# ACB-Light-R1_0-J05.net
KiCad netlist of a schematic drawn in EAGLE
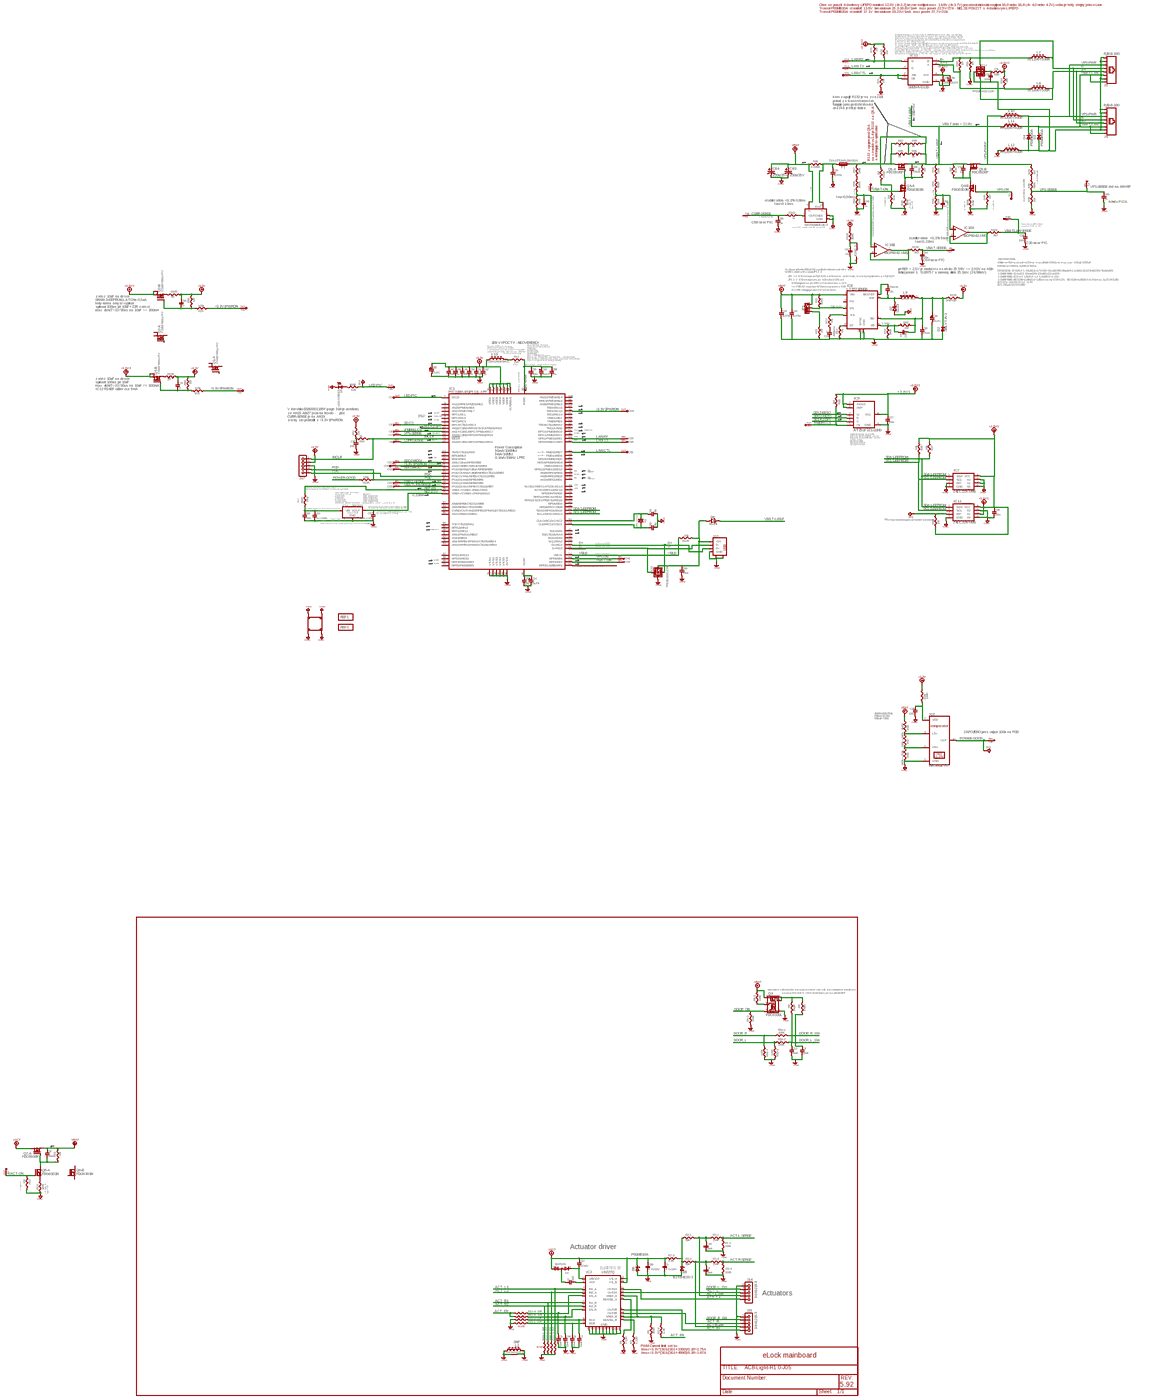
[diagram p0: schematic, sheet 1, overview]
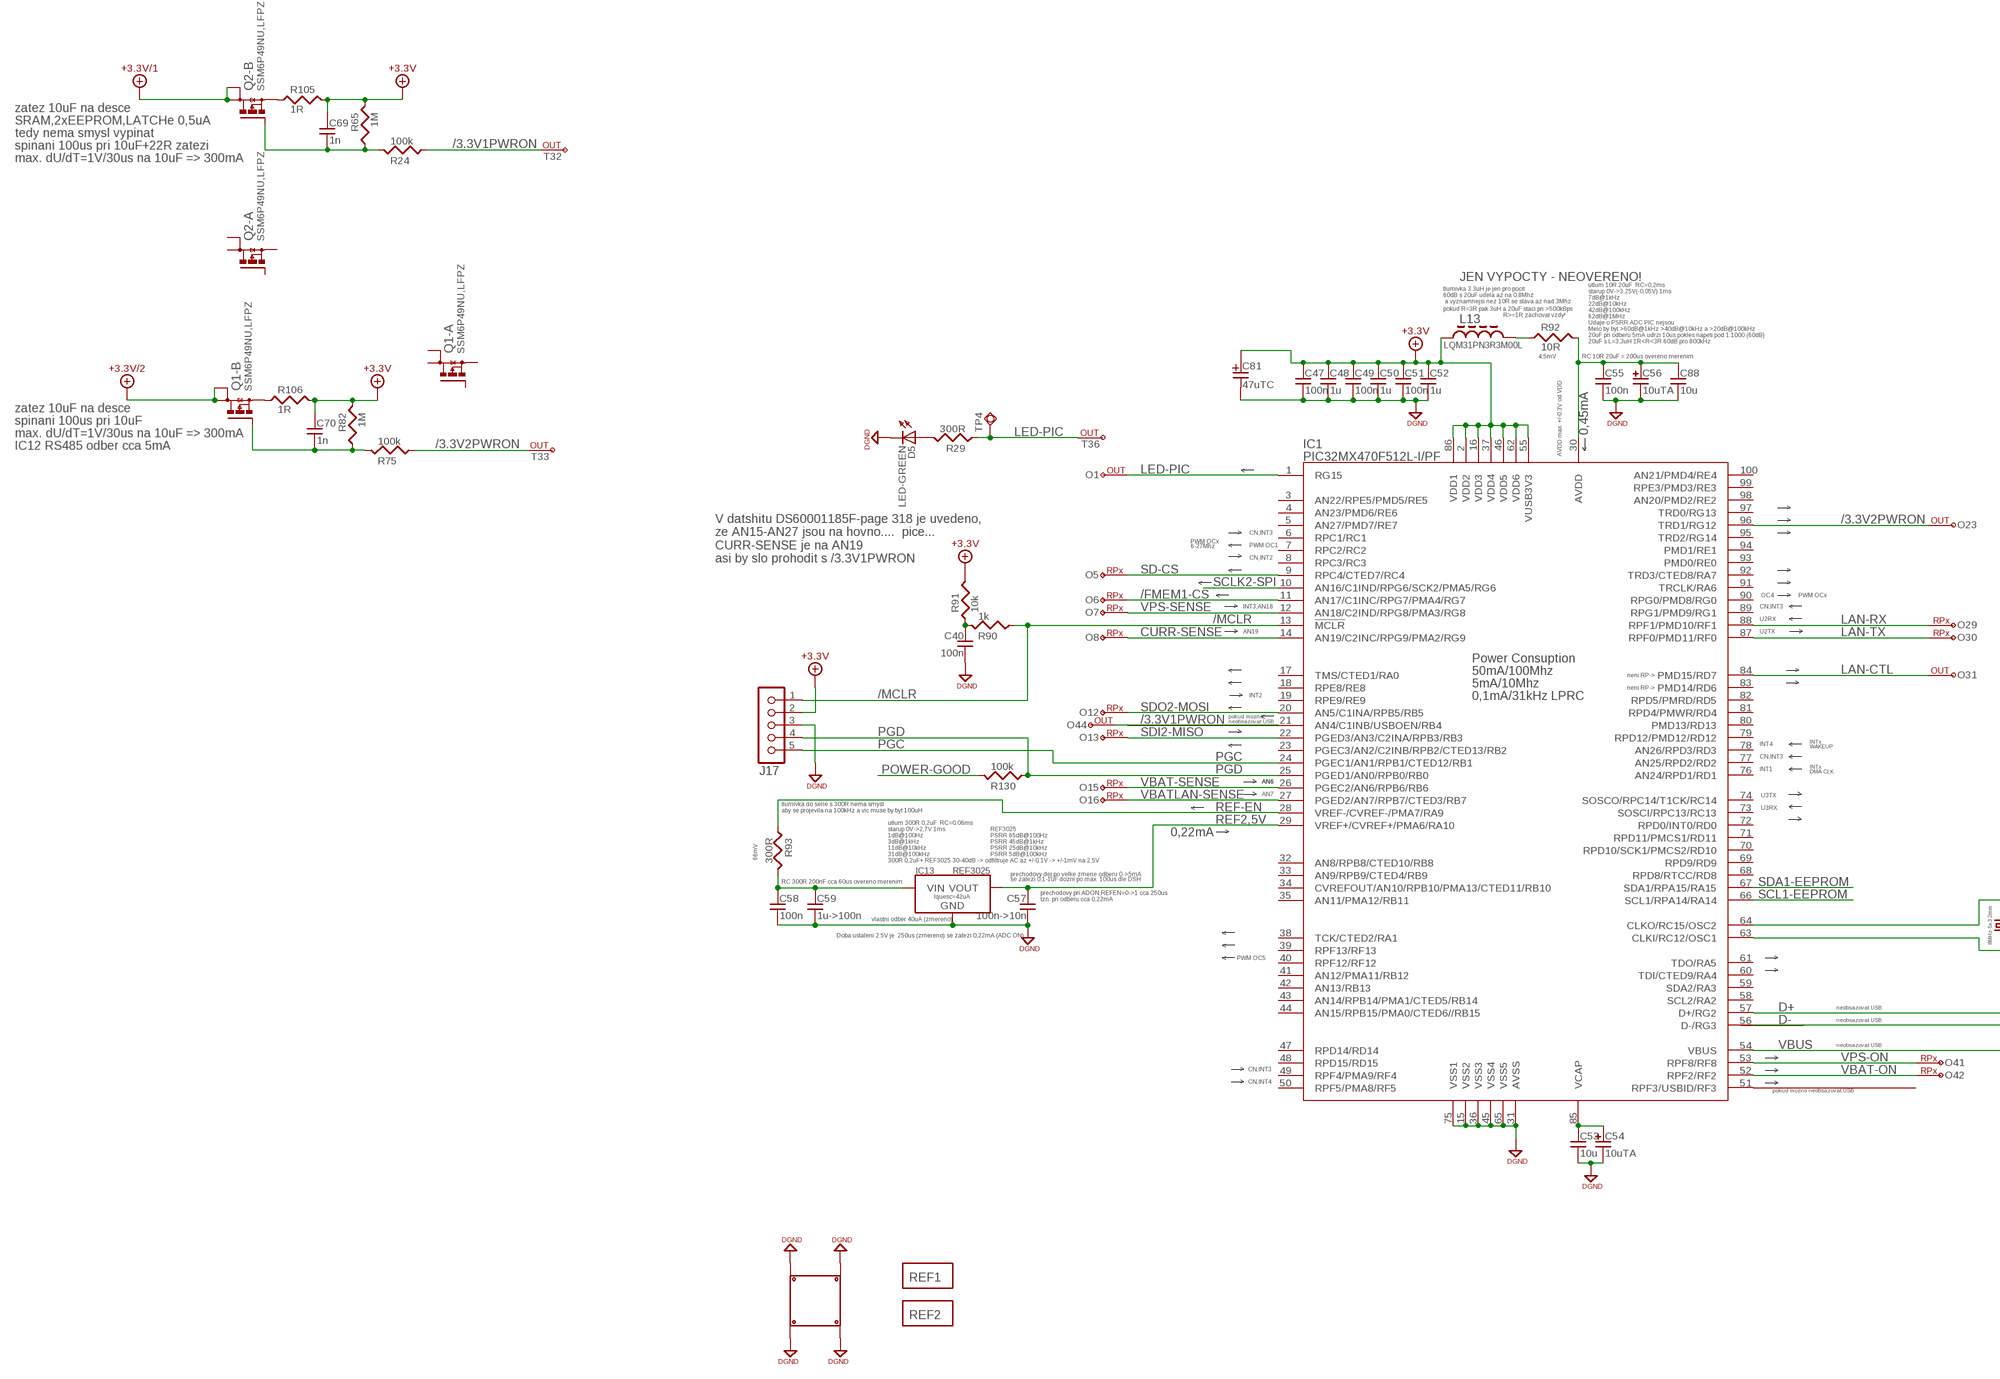
[diagram p1: schematic, sheet 1, part 1 of 5]
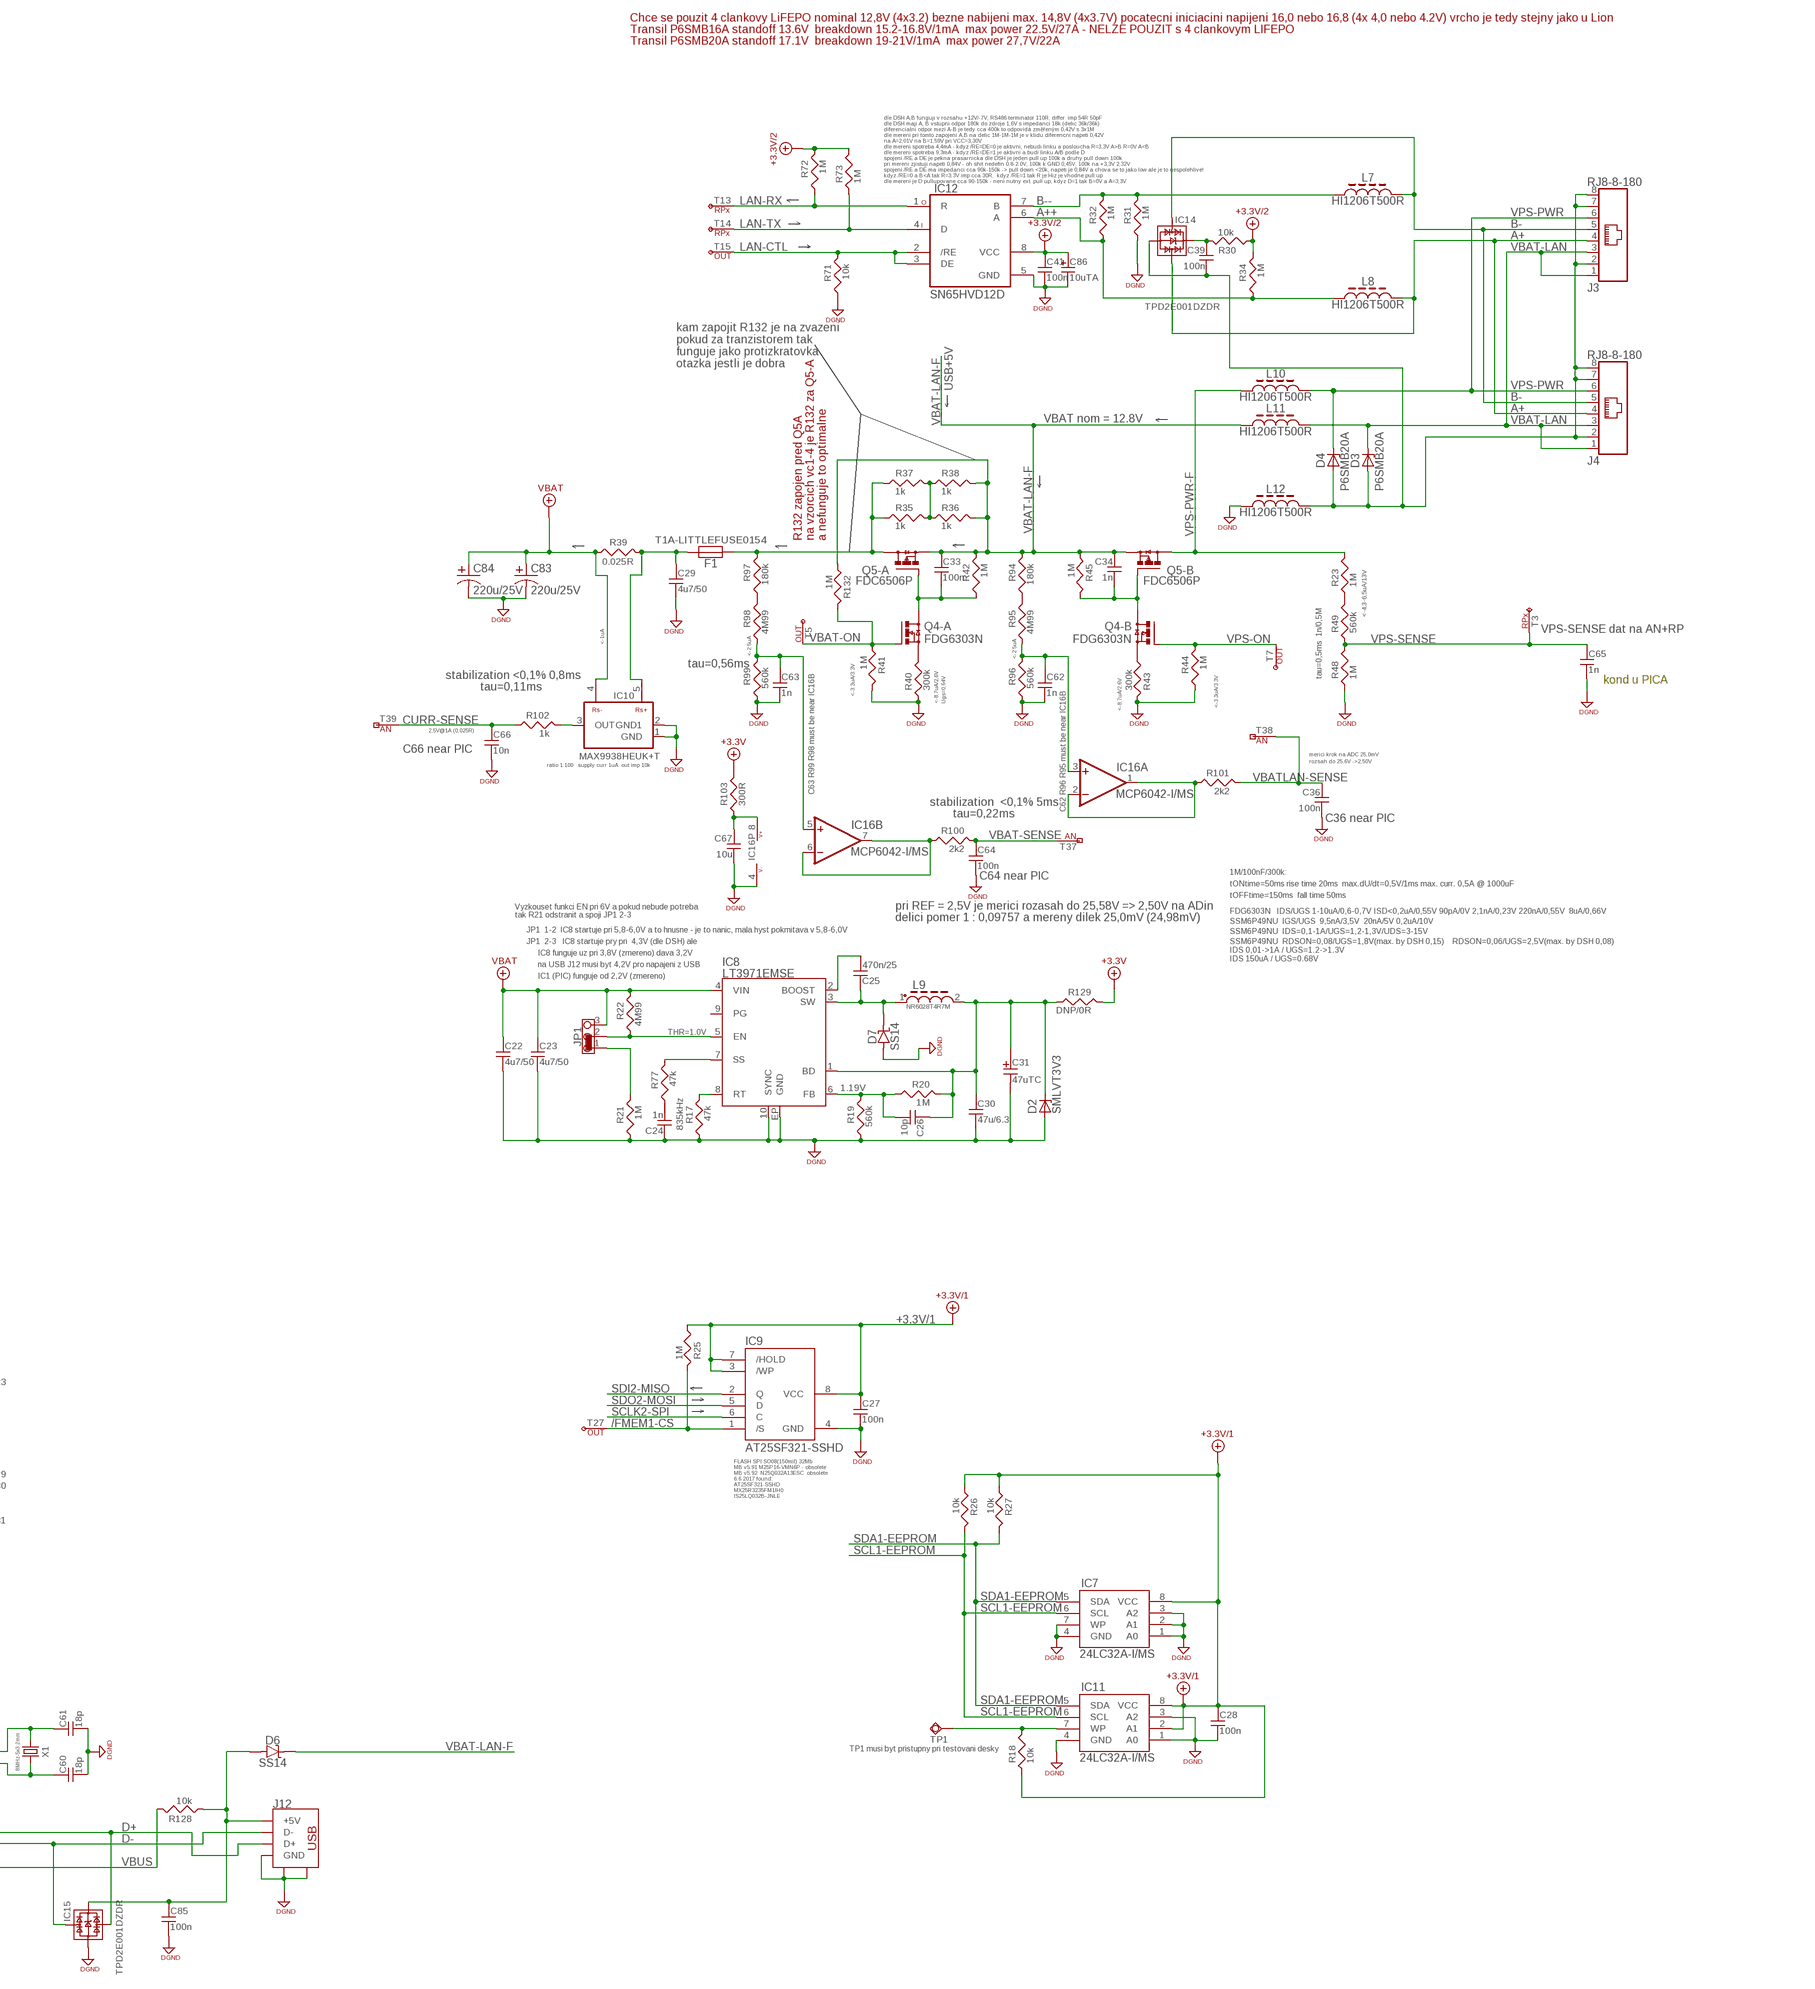
[diagram p2: schematic, sheet 1, part 2 of 5]
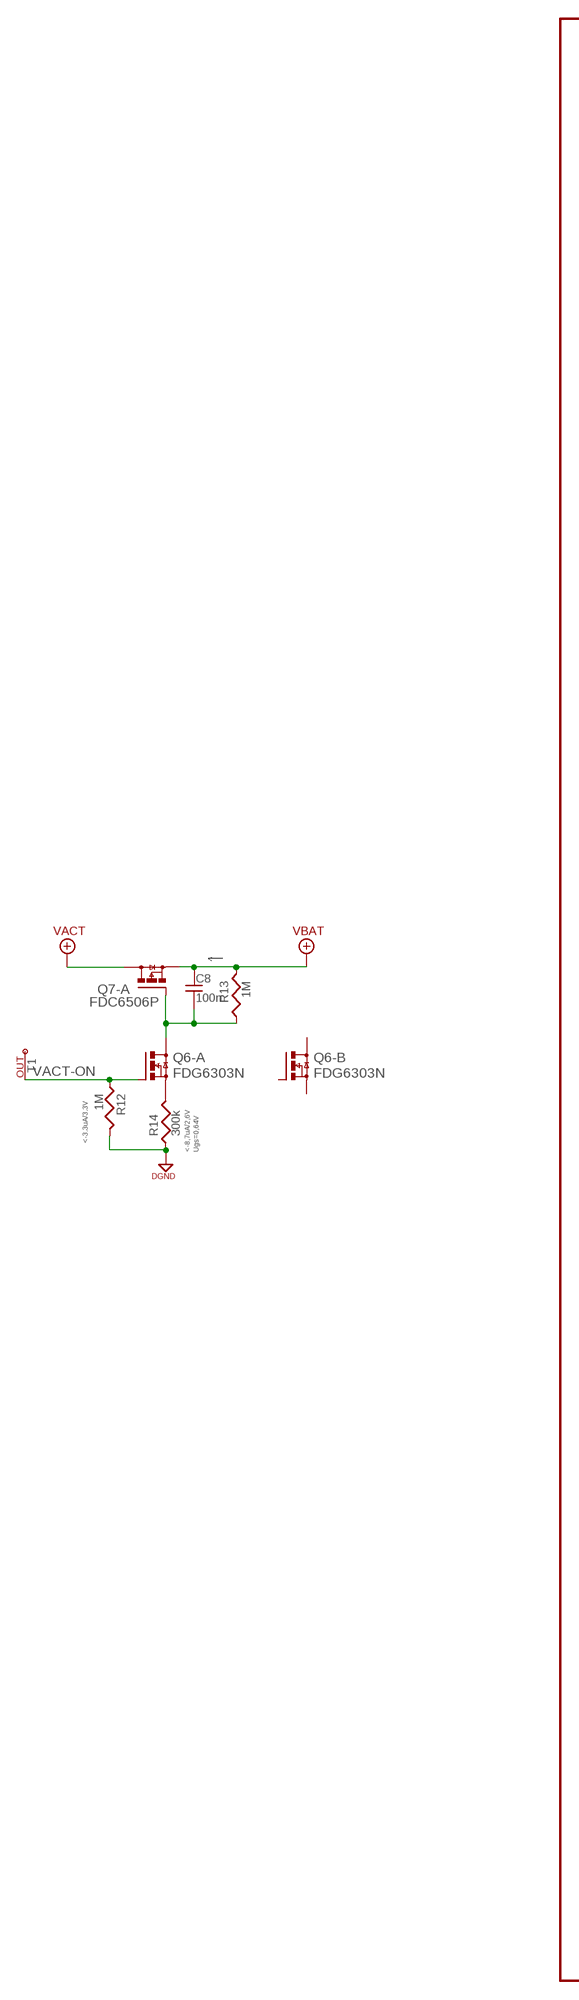
[diagram p3: schematic, sheet 1, part 3 of 5]
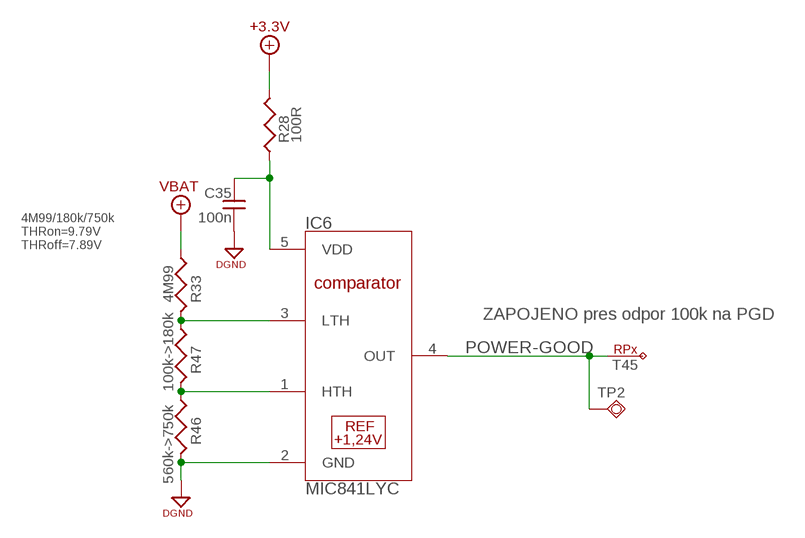
[diagram p4: schematic, sheet 1, part 4 of 5]
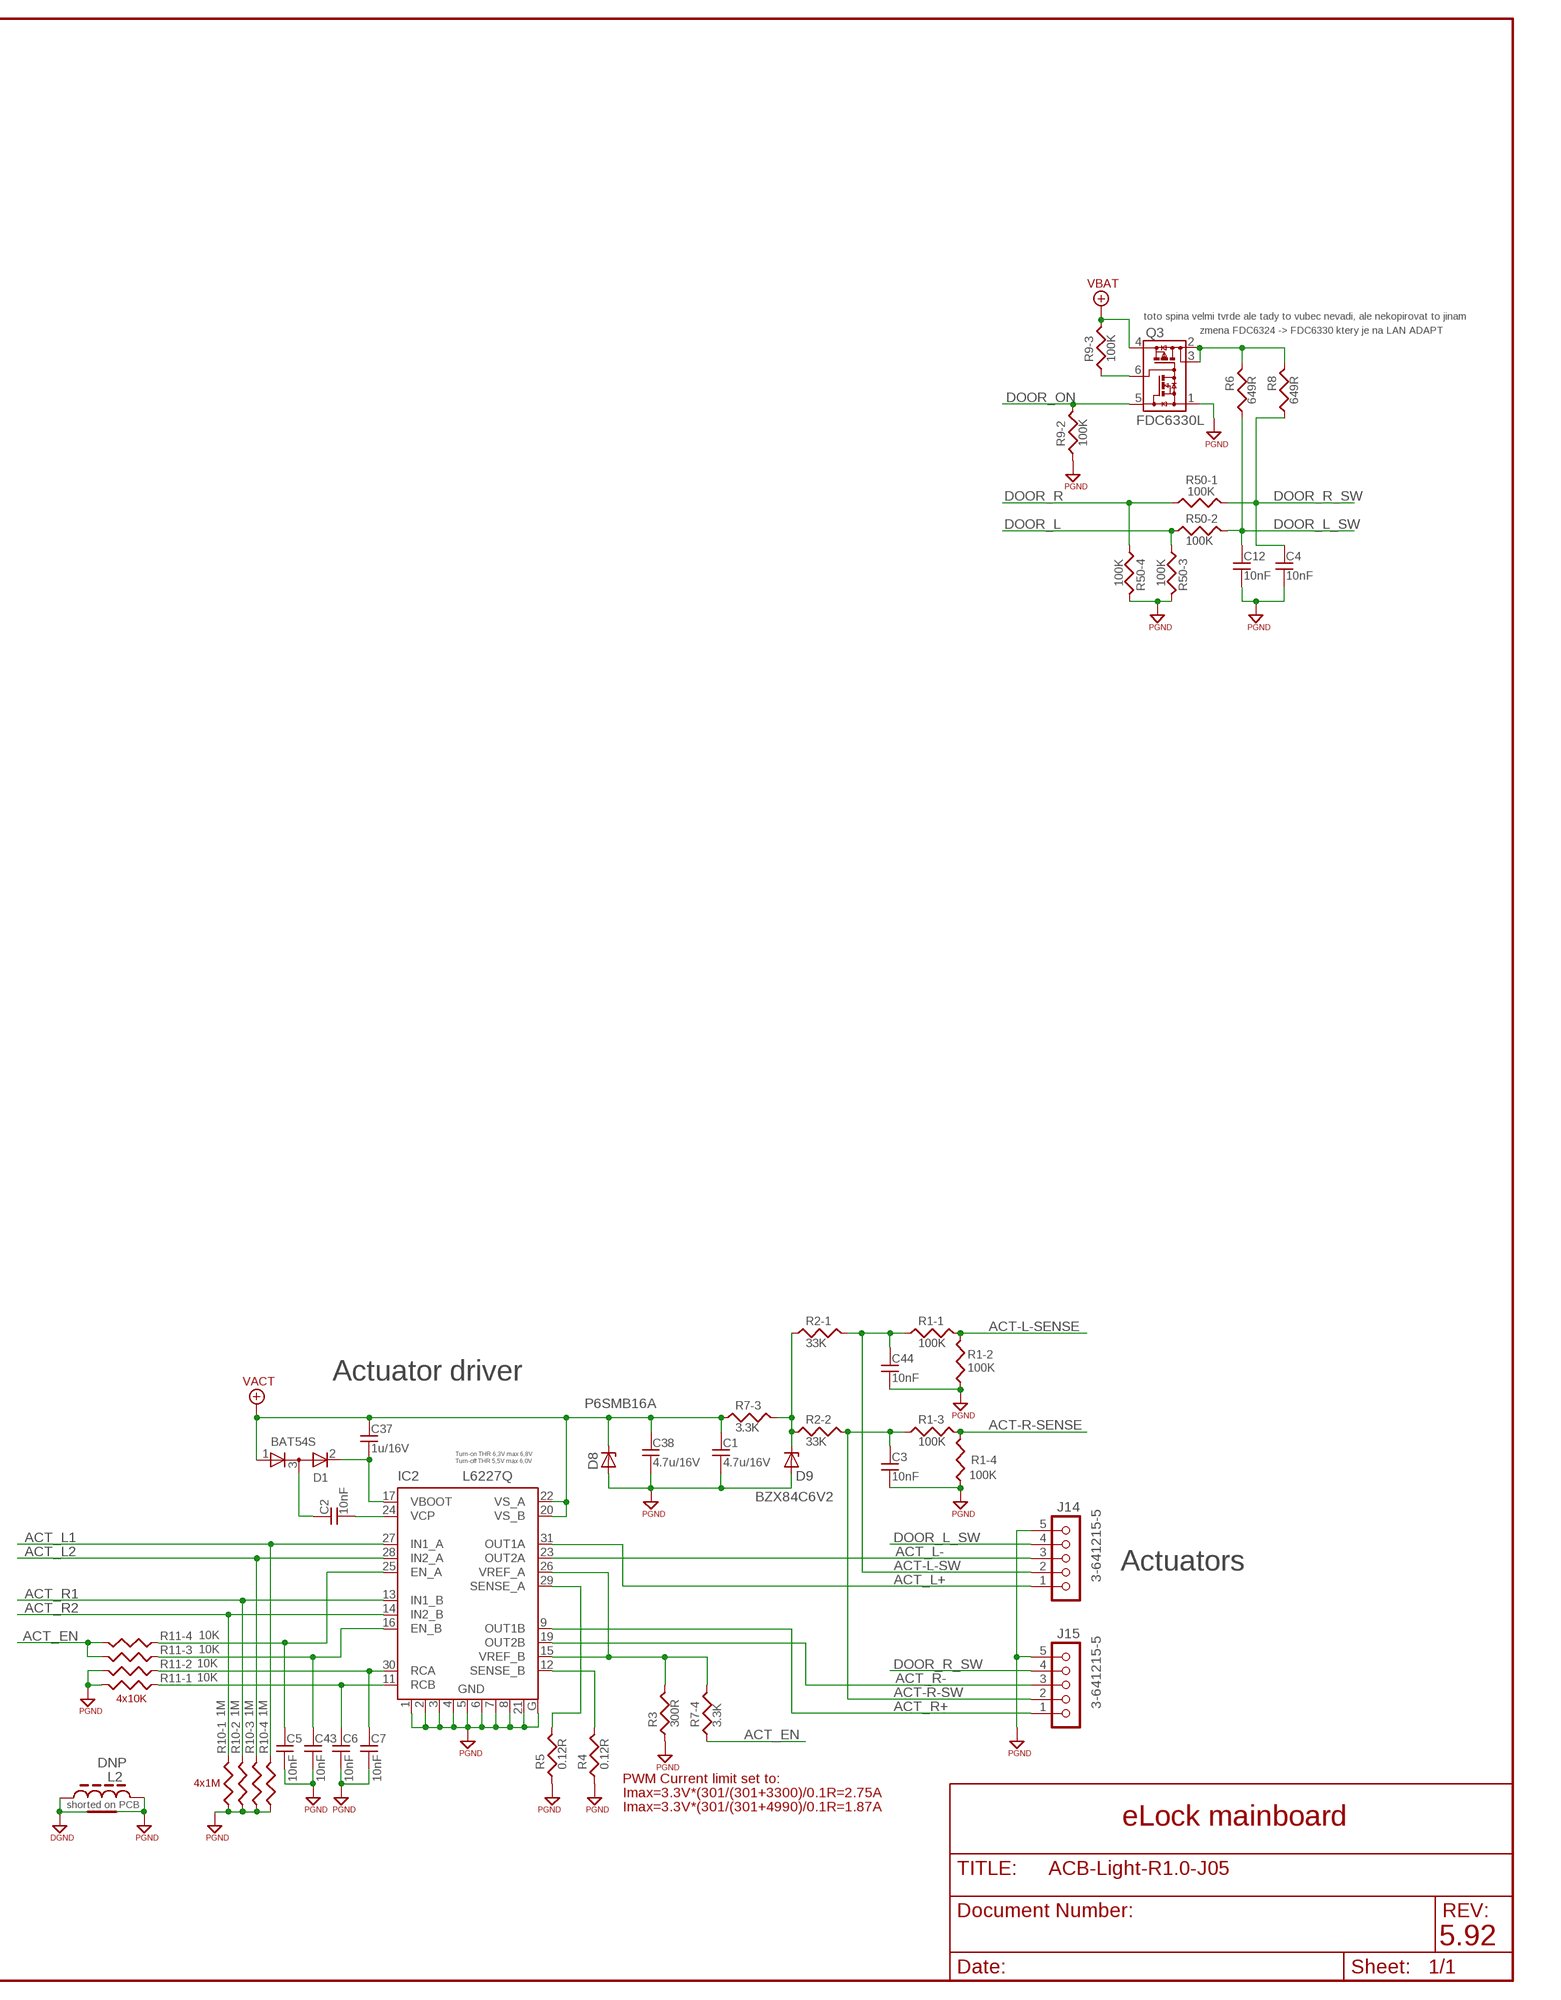
[diagram p5: schematic, sheet 1, part 5 of 5]

(export (version "E")
  (design (tool "Eeschema 10.0.6"))
  (components
    (comp (ref "C1")
      (value "4.7u/16V")
      (footprint "eagle-import:0805")
      (libsource (lib "eagle-import") (part "C-0805"))
    )
    (comp (ref "C2")
      (value "10nF")
      (footprint "eagle-import:0603")
      (libsource (lib "eagle-import") (part "C-0603"))
    )
    (comp (ref "C3")
      (value "10nF")
      (footprint "eagle-import:0603")
      (libsource (lib "eagle-import") (part "C-0603"))
    )
    (comp (ref "C4")
      (value "10nF")
      (footprint "eagle-import:0603")
      (libsource (lib "eagle-import") (part "C-0603"))
    )
    (comp (ref "C5")
      (value "10nF")
      (footprint "eagle-import:0603")
      (libsource (lib "eagle-import") (part "C-0603"))
    )
    (comp (ref "C6")
      (value "10nF")
      (footprint "eagle-import:0603")
      (libsource (lib "eagle-import") (part "C-0603"))
    )
    (comp (ref "C7")
      (value "10nF")
      (footprint "eagle-import:0603")
      (libsource (lib "eagle-import") (part "C-0603"))
    )
    (comp (ref "C8")
      (value "100n")
      (footprint "eagle-import:0603")
      (libsource (lib "eagle-import") (part "C-0603"))
    )
    (comp (ref "C12")
      (value "10nF")
      (footprint "eagle-import:0603")
      (libsource (lib "eagle-import") (part "C-0603"))
    )
    (comp (ref "C22")
      (value "4u7/50")
      (footprint "eagle-import:1206")
      (libsource (lib "eagle-import") (part "C-1206"))
    )
    (comp (ref "C23")
      (value "4u7/50")
      (footprint "eagle-import:1206")
      (libsource (lib "eagle-import") (part "C-1206"))
    )
    (comp (ref "C24")
      (value "1n")
      (footprint "eagle-import:0603")
      (libsource (lib "eagle-import") (part "C-0603"))
    )
    (comp (ref "C25")
      (value "470n/25")
      (footprint "eagle-import:0603")
      (libsource (lib "eagle-import") (part "C-0603"))
    )
    (comp (ref "C26")
      (value "10p")
      (footprint "eagle-import:0603")
      (libsource (lib "eagle-import") (part "C-0603"))
    )
    (comp (ref "C27")
      (value "100n")
      (footprint "eagle-import:0603")
      (libsource (lib "eagle-import") (part "C-0603"))
    )
    (comp (ref "C28")
      (value "100n")
      (footprint "eagle-import:0603")
      (libsource (lib "eagle-import") (part "C-0603"))
    )
    (comp (ref "C29")
      (value "4u7/50")
      (footprint "eagle-import:1206")
      (libsource (lib "eagle-import") (part "C-1206"))
    )
    (comp (ref "C30")
      (value "47u/6.3")
      (footprint "eagle-import:1206")
      (libsource (lib "eagle-import") (part "C-1206"))
    )
    (comp (ref "C31")
      (value "47uTC")
      (footprint "eagle-import:CT-C")
      (libsource (lib "eagle-import") (part "CT-C"))
    )
    (comp (ref "C33")
      (value "100n")
      (footprint "eagle-import:0603")
      (libsource (lib "eagle-import") (part "C-0603"))
    )
    (comp (ref "C34")
      (value "1n")
      (footprint "eagle-import:0603")
      (libsource (lib "eagle-import") (part "C-0603"))
    )
    (comp (ref "C35")
      (value "100n")
      (footprint "eagle-import:0603")
      (libsource (lib "eagle-import") (part "C-0603"))
    )
    (comp (ref "C36")
      (value "100n")
      (footprint "eagle-import:0603")
      (libsource (lib "eagle-import") (part "C-0603"))
    )
    (comp (ref "C37")
      (value "1u/16V")
      (footprint "eagle-import:0603")
      (libsource (lib "eagle-import") (part "C-0603"))
    )
    (comp (ref "C38")
      (value "4.7u/16V")
      (footprint "eagle-import:0805")
      (libsource (lib "eagle-import") (part "C-0805"))
    )
    (comp (ref "C39")
      (value "100n")
      (footprint "eagle-import:0603")
      (libsource (lib "eagle-import") (part "C-0603"))
    )
    (comp (ref "C40")
      (value "100n")
      (footprint "eagle-import:0603")
      (libsource (lib "eagle-import") (part "C-0603"))
    )
    (comp (ref "C41")
      (value "100n")
      (footprint "eagle-import:0603")
      (libsource (lib "eagle-import") (part "C-0603"))
    )
    (comp (ref "C43")
      (value "10nF")
      (footprint "eagle-import:0603")
      (libsource (lib "eagle-import") (part "C-0603"))
    )
    (comp (ref "C44")
      (value "10nF")
      (footprint "eagle-import:0603")
      (libsource (lib "eagle-import") (part "C-0603"))
    )
    (comp (ref "C47")
      (value "100n")
      (footprint "eagle-import:0603")
      (libsource (lib "eagle-import") (part "C-0603"))
    )
    (comp (ref "C48")
      (value "1u")
      (footprint "eagle-import:0603")
      (libsource (lib "eagle-import") (part "C-0603"))
    )
    (comp (ref "C49")
      (value "100n")
      (footprint "eagle-import:0603")
      (libsource (lib "eagle-import") (part "C-0603"))
    )
    (comp (ref "C50")
      (value "1u")
      (footprint "eagle-import:0603")
      (libsource (lib "eagle-import") (part "C-0603"))
    )
    (comp (ref "C51")
      (value "100n")
      (footprint "eagle-import:0603")
      (libsource (lib "eagle-import") (part "C-0603"))
    )
    (comp (ref "C52")
      (value "1u")
      (footprint "eagle-import:0603")
      (libsource (lib "eagle-import") (part "C-0603"))
    )
    (comp (ref "C53")
      (value "10u")
      (footprint "eagle-import:0603")
      (libsource (lib "eagle-import") (part "C-0603"))
    )
    (comp (ref "C54")
      (value "10uTA")
      (footprint "eagle-import:1206-POL-C")
      (libsource (lib "eagle-import") (part "CT-1206"))
    )
    (comp (ref "C55")
      (value "100n")
      (footprint "eagle-import:0603")
      (libsource (lib "eagle-import") (part "C-0603"))
    )
    (comp (ref "C56")
      (value "10uTA")
      (footprint "eagle-import:1206-POL-C")
      (libsource (lib "eagle-import") (part "CT-1206"))
    )
    (comp (ref "C57")
      (value "100n->10n")
      (footprint "eagle-import:0603")
      (libsource (lib "eagle-import") (part "C-0603"))
    )
    (comp (ref "C58")
      (value "100n")
      (footprint "eagle-import:0603")
      (libsource (lib "eagle-import") (part "C-0603"))
    )
    (comp (ref "C59")
      (value "1u->100n")
      (footprint "eagle-import:0603")
      (libsource (lib "eagle-import") (part "C-0603"))
    )
    (comp (ref "C60")
      (value "18p")
      (footprint "eagle-import:0603")
      (libsource (lib "eagle-import") (part "C-0603"))
    )
    (comp (ref "C61")
      (value "18p")
      (footprint "eagle-import:0603")
      (libsource (lib "eagle-import") (part "C-0603"))
    )
    (comp (ref "C62")
      (value "1n")
      (footprint "eagle-import:0603")
      (libsource (lib "eagle-import") (part "C-0603"))
    )
    (comp (ref "C63")
      (value "1n")
      (footprint "eagle-import:0603")
      (libsource (lib "eagle-import") (part "C-0603"))
    )
    (comp (ref "C64")
      (value "100n")
      (footprint "eagle-import:0603")
      (libsource (lib "eagle-import") (part "C-0603"))
    )
    (comp (ref "C65")
      (value "1n")
      (footprint "eagle-import:0603")
      (libsource (lib "eagle-import") (part "C-0603"))
    )
    (comp (ref "C66")
      (value "10n")
      (footprint "eagle-import:0603")
      (libsource (lib "eagle-import") (part "C-0603"))
    )
    (comp (ref "C67")
      (value "10u")
      (footprint "eagle-import:0603")
      (libsource (lib "eagle-import") (part "C-0603"))
    )
    (comp (ref "C69")
      (value "1n")
      (footprint "eagle-import:0603")
      (libsource (lib "eagle-import") (part "C-0603"))
    )
    (comp (ref "C70")
      (value "1n")
      (footprint "eagle-import:0603")
      (libsource (lib "eagle-import") (part "C-0603"))
    )
    (comp (ref "C81")
      (value "47uTC")
      (footprint "eagle-import:CT-C")
      (libsource (lib "eagle-import") (part "CT-C"))
    )
    (comp (ref "C83")
      (value "220u/25V")
      (footprint "eagle-import:CAP_8MM_DIA_SMT")
      (libsource (lib "eagle-import") (part "CAP-ELEC-SMD-8MM"))
    )
    (comp (ref "C84")
      (value "220u/25V")
      (footprint "eagle-import:CAP_8MM_DIA_SMT")
      (libsource (lib "eagle-import") (part "CAP-ELEC-SMD-8MM"))
    )
    (comp (ref "C85")
      (value "100n")
      (footprint "eagle-import:0603")
      (libsource (lib "eagle-import") (part "C-0603"))
    )
    (comp (ref "C86")
      (value "10uTA")
      (footprint "eagle-import:1206-POL-C")
      (libsource (lib "eagle-import") (part "CT-1206"))
    )
    (comp (ref "C88")
      (value "10u")
      (footprint "eagle-import:0603")
      (libsource (lib "eagle-import") (part "C-0603"))
    )
    (comp (ref "D1")
      (value "BAT54S")
      (footprint "eagle-import:SOT-23")
      (libsource (lib "eagle-import") (part "BAT54S"))
    )
    (comp (ref "D2")
      (value "SMLVT3V3")
      (footprint "eagle-import:SMA")
      (libsource (lib "eagle-import") (part "SMLVT3V3"))
    )
    (comp (ref "D3")
      (value "P6SMB20A")
      (footprint "eagle-import:SMB")
      (libsource (lib "eagle-import") (part "P6SMB"))
    )
    (comp (ref "D4")
      (value "P6SMB20A")
      (footprint "eagle-import:SMB")
      (libsource (lib "eagle-import") (part "P6SMB"))
    )
    (comp (ref "D5")
      (value "LED-GREEN")
      (footprint "eagle-import:0805-POL-D")
      (libsource (lib "eagle-import") (part "LED-0805"))
    )
    (comp (ref "D6")
      (value "SS14")
      (footprint "eagle-import:SMA")
      (libsource (lib "eagle-import") (part "DS-SMA"))
    )
    (comp (ref "D7")
      (value "SS14")
      (footprint "eagle-import:SMA")
      (libsource (lib "eagle-import") (part "DS-SMA"))
    )
    (comp (ref "D8")
      (value "P6SMB16A")
      (footprint "eagle-import:SMB")
      (libsource (lib "eagle-import") (part "P6SMB"))
    )
    (comp (ref "D9")
      (value "BZX84C6V2")
      (footprint "eagle-import:SOT-23")
      (libsource (lib "eagle-import") (part "BZX84C6V2"))
    )
    (comp (ref "F1")
      (value "T1A-LITTLEFUSE0154")
      (footprint "eagle-import:LITTLEFUSE0154")
      (libsource (lib "eagle-import") (part "POJISTKA-LITTLEFUSE0154"))
    )
    (comp (ref "IC1")
      (value "PIC32MX470F512L-I/PF")
      (footprint "eagle-import:TQFP100_14X14_0,5MM")
      (libsource (lib "eagle-import") (part "PIC32MX470F512L-I/PF"))
    )
    (comp (ref "IC2")
      (value "L6227Q")
      (footprint "eagle-import:SQFP-S-5X5-32")
      (libsource (lib "eagle-import") (part "L6227Q"))
    )
    (comp (ref "IC6")
      (value "MIC841LYC")
      (footprint "eagle-import:SC-70-5")
      (libsource (lib "eagle-import") (part "MIC841LYC"))
    )
    (comp (ref "IC7")
      (value "24LC32A-I/MS")
      (footprint "eagle-import:MSOP-08")
      (libsource (lib "eagle-import") (part "24-I/MS"))
    )
    (comp (ref "IC8")
      (value "LT3971EMSE")
      (footprint "eagle-import:MSOP10EXP")
      (libsource (lib "eagle-import") (part "LT3971EMSE"))
    )
    (comp (ref "IC9")
      (value "AT25SF321-SSHD")
      (footprint "eagle-import:SO-08")
      (libsource (lib "eagle-import") (part "M25P16-VMN6P"))
    )
    (comp (ref "IC10")
      (value "MAX9938HEUK+T")
      (footprint "eagle-import:SOT23-5")
      (libsource (lib "eagle-import") (part "TSM9938HEUK+T"))
    )
    (comp (ref "IC11")
      (value "24LC32A-I/MS")
      (footprint "eagle-import:MSOP-08")
      (libsource (lib "eagle-import") (part "24-I/MS"))
    )
    (comp (ref "IC12")
      (value "SN65HVD12D")
      (footprint "eagle-import:SO08")
      (libsource (lib "eagle-import") (part "SN65HVD3082ED"))
    )
    (comp (ref "IC13")
      (value "REF3025")
      (footprint "eagle-import:SOT23")
      (libsource (lib "eagle-import") (part "REF3025"))
    )
    (comp (ref "IC14")
      (value "TPD2E001DZDR")
      (footprint "eagle-import:SOT-143")
      (libsource (lib "eagle-import") (part "SR05.TCT"))
    )
    (comp (ref "IC15")
      (value "TPD2E001DZDR")
      (footprint "eagle-import:SOT-143")
      (libsource (lib "eagle-import") (part "SR05.TCT"))
    )
    (comp (ref "IC16")
      (value "MCP6042-I/MS")
      (footprint "eagle-import:MSOP-08")
      (libsource (lib "eagle-import") (part "MCP6042-I/MS"))
    )
    (comp (ref "J3")
      (value "RJ8-8-180")
      (footprint "eagle-import:RJ8-8-180")
      (libsource (lib "eagle-import") (part "RJ8-8-180"))
    )
    (comp (ref "J4")
      (value "RJ8-8-180")
      (footprint "eagle-import:RJ8-8-180")
      (libsource (lib "eagle-import") (part "RJ8-8-180"))
    )
    (comp (ref "J12")
      (value "USB_A_180")
      (footprint "eagle-import:USB_B_180")
      (libsource (lib "eagle-import") (part "USB_B_180"))
    )
    (comp (ref "J14")
      (value "3-641215-5")
      (footprint "eagle-import:3-641215-5")
      (libsource (lib "eagle-import") (part "3-641215-5"))
    )
    (comp (ref "J15")
      (value "3-641215-5")
      (footprint "eagle-import:3-641215-5")
      (libsource (lib "eagle-import") (part "3-641215-5"))
    )
    (comp (ref "J17")
      (value "DNP-open-hole")
      (footprint "eagle-import:MA05-1")
      (libsource (lib "eagle-import") (part "MA05-1"))
    )
    (comp (ref "JP1")
      (value "JP3CLOSE12")
      (footprint "eagle-import:JP3CLOSE12")
      (libsource (lib "eagle-import") (part "JP3CLOSE12"))
    )
    (comp (ref "L2")
      (value "DNP")
      (footprint "eagle-import:0805-0RTOP")
      (libsource (lib "eagle-import") (part "L-0805-0R"))
    )
    (comp (ref "L7")
      (value "HI1206T500R")
      (footprint "eagle-import:1206")
      (libsource (lib "eagle-import") (part "L-1206"))
    )
    (comp (ref "L8")
      (value "HI1206T500R")
      (footprint "eagle-import:1206")
      (libsource (lib "eagle-import") (part "L-1206"))
    )
    (comp (ref "L9")
      (value "NR6028T4R7M")
      (footprint "eagle-import:NR6028")
      (libsource (lib "eagle-import") (part "NR6028"))
    )
    (comp (ref "L10")
      (value "HI1206T500R")
      (footprint "eagle-import:1206")
      (libsource (lib "eagle-import") (part "L-1206"))
    )
    (comp (ref "L11")
      (value "HI1206T500R")
      (footprint "eagle-import:1206")
      (libsource (lib "eagle-import") (part "L-1206"))
    )
    (comp (ref "L12")
      (value "HI1206T500R")
      (footprint "eagle-import:1206")
      (libsource (lib "eagle-import") (part "L-1206"))
    )
    (comp (ref "L13")
      (value "LQM31PN3R3M00L")
      (footprint "eagle-import:1206")
      (libsource (lib "eagle-import") (part "L-1206"))
    )
    (comp (ref "O1")
      (value "PIC-OUT")
      (footprint "eagle-import:TEMP-PAD")
      (libsource (lib "eagle-import") (part "PIC-OUT"))
    )
    (comp (ref "O5")
      (value "PIC-RPX")
      (footprint "eagle-import:TEMP-PAD")
      (libsource (lib "eagle-import") (part "PIC-RPX"))
    )
    (comp (ref "O6")
      (value "PIC-RPX")
      (footprint "eagle-import:TEMP-PAD")
      (libsource (lib "eagle-import") (part "PIC-RPX"))
    )
    (comp (ref "O7")
      (value "PIC-RPX")
      (footprint "eagle-import:TEMP-PAD")
      (libsource (lib "eagle-import") (part "PIC-RPX"))
    )
    (comp (ref "O8")
      (value "PIC-RPX")
      (footprint "eagle-import:TEMP-PAD")
      (libsource (lib "eagle-import") (part "PIC-RPX"))
    )
    (comp (ref "O12")
      (value "PIC-RPX")
      (footprint "eagle-import:TEMP-PAD")
      (libsource (lib "eagle-import") (part "PIC-RPX"))
    )
    (comp (ref "O13")
      (value "PIC-RPX")
      (footprint "eagle-import:TEMP-PAD")
      (libsource (lib "eagle-import") (part "PIC-RPX"))
    )
    (comp (ref "O15")
      (value "PIC-RPX")
      (footprint "eagle-import:TEMP-PAD")
      (libsource (lib "eagle-import") (part "PIC-RPX"))
    )
    (comp (ref "O16")
      (value "PIC-RPX")
      (footprint "eagle-import:TEMP-PAD")
      (libsource (lib "eagle-import") (part "PIC-RPX"))
    )
    (comp (ref "O23")
      (value "PIC-OUT")
      (footprint "eagle-import:TEMP-PAD")
      (libsource (lib "eagle-import") (part "PIC-OUT"))
    )
    (comp (ref "O29")
      (value "PIC-RPX")
      (footprint "eagle-import:TEMP-PAD")
      (libsource (lib "eagle-import") (part "PIC-RPX"))
    )
    (comp (ref "O30")
      (value "PIC-RPX")
      (footprint "eagle-import:TEMP-PAD")
      (libsource (lib "eagle-import") (part "PIC-RPX"))
    )
    (comp (ref "O31")
      (value "PIC-OUT")
      (footprint "eagle-import:TEMP-PAD")
      (libsource (lib "eagle-import") (part "PIC-OUT"))
    )
    (comp (ref "O41")
      (value "PIC-RPX")
      (footprint "eagle-import:TEMP-PAD")
      (libsource (lib "eagle-import") (part "PIC-RPX"))
    )
    (comp (ref "O42")
      (value "PIC-RPX")
      (footprint "eagle-import:TEMP-PAD")
      (libsource (lib "eagle-import") (part "PIC-RPX"))
    )
    (comp (ref "O44")
      (value "PIC-OUT")
      (footprint "eagle-import:TEMP-PAD")
      (libsource (lib "eagle-import") (part "PIC-OUT"))
    )
    (comp (ref "PCB1")
      (value "PCB-ACB")
      (footprint "eagle-import:PCB-ACB")
      (libsource (lib "eagle-import") (part "PCB-ACB-1"))
    )
    (comp (ref "Q1")
      (value "SSM6P49NU,LFPZ")
      (footprint "eagle-import:MICRO_FET")
      (libsource (lib "eagle-import") (part "SSM6P49PZNU,LF"))
    )
    (comp (ref "Q2")
      (value "SSM6P49NU,LFPZ")
      (footprint "eagle-import:MICRO_FET")
      (libsource (lib "eagle-import") (part "SSM6P49PZNU,LF"))
    )
    (comp (ref "Q3")
      (value "FDC6330L")
      (footprint "eagle-import:SSOT-6")
      (libsource (lib "eagle-import") (part "FDC6330L"))
    )
    (comp (ref "Q4")
      (value "FDG6303N")
      (footprint "eagle-import:SC70-6")
      (libsource (lib "eagle-import") (part "FDG6303N"))
    )
    (comp (ref "Q5")
      (value "FDC6506P")
      (footprint "eagle-import:SSOT-6")
      (libsource (lib "eagle-import") (part "FDC6506D"))
    )
    (comp (ref "Q6")
      (value "FDG6303N")
      (footprint "eagle-import:SC70-6")
      (libsource (lib "eagle-import") (part "FDG6303N"))
    )
    (comp (ref "Q7")
      (value "FDC6506P")
      (footprint "eagle-import:SSOT-6")
      (libsource (lib "eagle-import") (part "FDC6506D"))
    )
    (comp (ref "R1")
      (value "100K")
      (footprint "eagle-import:0603-ARRAY")
      (libsource (lib "eagle-import") (part "EXB-38"))
    )
    (comp (ref "R2")
      (value "33K")
      (footprint "eagle-import:0603-ARRAY")
      (libsource (lib "eagle-import") (part "EXB-38"))
    )
    (comp (ref "R3")
      (value "300R")
      (footprint "eagle-import:0603")
      (libsource (lib "eagle-import") (part "R-0603"))
    )
    (comp (ref "R4")
      (value "0.12R")
      (footprint "eagle-import:0805")
      (libsource (lib "eagle-import") (part "R-0805"))
    )
    (comp (ref "R5")
      (value "0.12R")
      (footprint "eagle-import:0805")
      (libsource (lib "eagle-import") (part "R-0805"))
    )
    (comp (ref "R6")
      (value "649R")
      (footprint "eagle-import:0603")
      (libsource (lib "eagle-import") (part "R-0603"))
    )
    (comp (ref "R7")
      (value "3.3K")
      (footprint "eagle-import:0603-ARRAY")
      (libsource (lib "eagle-import") (part "EXB-38"))
    )
    (comp (ref "R8")
      (value "649R")
      (footprint "eagle-import:0603")
      (libsource (lib "eagle-import") (part "R-0603"))
    )
    (comp (ref "R9")
      (value "100K")
      (footprint "eagle-import:0603-ARRAY")
      (libsource (lib "eagle-import") (part "EXB-38"))
    )
    (comp (ref "R10")
      (value "1M")
      (footprint "eagle-import:0603-ARRAY")
      (libsource (lib "eagle-import") (part "EXB-38"))
    )
    (comp (ref "R11")
      (value "10K")
      (footprint "eagle-import:0603-ARRAY")
      (libsource (lib "eagle-import") (part "EXB-38"))
    )
    (comp (ref "R12")
      (value "1M")
      (footprint "eagle-import:0603")
      (libsource (lib "eagle-import") (part "R-0603"))
    )
    (comp (ref "R13")
      (value "1M")
      (footprint "eagle-import:0603")
      (libsource (lib "eagle-import") (part "R-0603"))
    )
    (comp (ref "R14")
      (value "300k")
      (footprint "eagle-import:0603")
      (libsource (lib "eagle-import") (part "R-0603"))
    )
    (comp (ref "R17")
      (value "47k")
      (footprint "eagle-import:0603")
      (libsource (lib "eagle-import") (part "R-0603"))
    )
    (comp (ref "R18")
      (value "10k")
      (footprint "eagle-import:0603")
      (libsource (lib "eagle-import") (part "R-0603"))
    )
    (comp (ref "R19")
      (value "560k")
      (footprint "eagle-import:0603")
      (libsource (lib "eagle-import") (part "R-0603"))
    )
    (comp (ref "R20")
      (value "1M")
      (footprint "eagle-import:0603")
      (libsource (lib "eagle-import") (part "R-0603"))
    )
    (comp (ref "R21")
      (value "1M")
      (footprint "eagle-import:0603")
      (libsource (lib "eagle-import") (part "R-0603"))
    )
    (comp (ref "R22")
      (value "4M99")
      (footprint "eagle-import:0603")
      (libsource (lib "eagle-import") (part "R-0603"))
    )
    (comp (ref "R23")
      (value "1M")
      (footprint "eagle-import:0603")
      (libsource (lib "eagle-import") (part "R-0603"))
    )
    (comp (ref "R24")
      (value "100k")
      (footprint "eagle-import:0603")
      (libsource (lib "eagle-import") (part "R-0603"))
    )
    (comp (ref "R25")
      (value "1M")
      (footprint "eagle-import:0603")
      (libsource (lib "eagle-import") (part "R-0603"))
    )
    (comp (ref "R26")
      (value "10k")
      (footprint "eagle-import:0603")
      (libsource (lib "eagle-import") (part "R-0603"))
    )
    (comp (ref "R27")
      (value "10k")
      (footprint "eagle-import:0603")
      (libsource (lib "eagle-import") (part "R-0603"))
    )
    (comp (ref "R28")
      (value "100R")
      (footprint "eagle-import:0603")
      (libsource (lib "eagle-import") (part "R-0603"))
    )
    (comp (ref "R29")
      (value "300R")
      (footprint "eagle-import:0603")
      (libsource (lib "eagle-import") (part "R-0603"))
    )
    (comp (ref "R30")
      (value "10k")
      (footprint "eagle-import:0603")
      (libsource (lib "eagle-import") (part "R-0603"))
    )
    (comp (ref "R31")
      (value "1M")
      (footprint "eagle-import:0603")
      (libsource (lib "eagle-import") (part "R-0603"))
    )
    (comp (ref "R32")
      (value "1M")
      (footprint "eagle-import:0603")
      (libsource (lib "eagle-import") (part "R-0603"))
    )
    (comp (ref "R33")
      (value "4M99")
      (footprint "eagle-import:0603")
      (libsource (lib "eagle-import") (part "R-0603"))
    )
    (comp (ref "R34")
      (value "1M")
      (footprint "eagle-import:0603")
      (libsource (lib "eagle-import") (part "R-0603"))
    )
    (comp (ref "R35")
      (value "1k")
      (footprint "eagle-import:0805")
      (libsource (lib "eagle-import") (part "R-0805"))
    )
    (comp (ref "R36")
      (value "1k")
      (footprint "eagle-import:0805")
      (libsource (lib "eagle-import") (part "R-0805"))
    )
    (comp (ref "R37")
      (value "1k")
      (footprint "eagle-import:0805")
      (libsource (lib "eagle-import") (part "R-0805"))
    )
    (comp (ref "R38")
      (value "1k")
      (footprint "eagle-import:0805")
      (libsource (lib "eagle-import") (part "R-0805"))
    )
    (comp (ref "R39")
      (value "0.025R")
      (footprint "eagle-import:0805")
      (libsource (lib "eagle-import") (part "R-0805"))
    )
    (comp (ref "R40")
      (value "300k")
      (footprint "eagle-import:0603")
      (libsource (lib "eagle-import") (part "R-0603"))
    )
    (comp (ref "R41")
      (value "1M")
      (footprint "eagle-import:0603")
      (libsource (lib "eagle-import") (part "R-0603"))
    )
    (comp (ref "R42")
      (value "1M")
      (footprint "eagle-import:0603")
      (libsource (lib "eagle-import") (part "R-0603"))
    )
    (comp (ref "R43")
      (value "300k")
      (footprint "eagle-import:0603")
      (libsource (lib "eagle-import") (part "R-0603"))
    )
    (comp (ref "R44")
      (value "1M")
      (footprint "eagle-import:0603")
      (libsource (lib "eagle-import") (part "R-0603"))
    )
    (comp (ref "R45")
      (value "1M")
      (footprint "eagle-import:0603")
      (libsource (lib "eagle-import") (part "R-0603"))
    )
    (comp (ref "R46")
      (value "560k->750k")
      (footprint "eagle-import:0603")
      (libsource (lib "eagle-import") (part "R-0603"))
    )
    (comp (ref "R47")
      (value "100k->180k")
      (footprint "eagle-import:0603")
      (libsource (lib "eagle-import") (part "R-0603"))
    )
    (comp (ref "R48")
      (value "1M")
      (footprint "eagle-import:0603")
      (libsource (lib "eagle-import") (part "R-0603"))
    )
    (comp (ref "R49")
      (value "560k")
      (footprint "eagle-import:0603")
      (libsource (lib "eagle-import") (part "R-0603"))
    )
    (comp (ref "R50")
      (value "100K")
      (footprint "eagle-import:0603-ARRAY")
      (libsource (lib "eagle-import") (part "EXB-38"))
    )
    (comp (ref "R65")
      (value "1M")
      (footprint "eagle-import:0603")
      (libsource (lib "eagle-import") (part "R-0603"))
    )
    (comp (ref "R71")
      (value "10k")
      (footprint "eagle-import:0603")
      (libsource (lib "eagle-import") (part "R-0603"))
    )
    (comp (ref "R72")
      (value "1M")
      (footprint "eagle-import:0603")
      (libsource (lib "eagle-import") (part "R-0603"))
    )
    (comp (ref "R73")
      (value "1M")
      (footprint "eagle-import:0603")
      (libsource (lib "eagle-import") (part "R-0603"))
    )
    (comp (ref "R75")
      (value "100k")
      (footprint "eagle-import:0603")
      (libsource (lib "eagle-import") (part "R-0603"))
    )
    (comp (ref "R77")
      (value "47k")
      (footprint "eagle-import:0603")
      (libsource (lib "eagle-import") (part "R-0603"))
    )
    (comp (ref "R82")
      (value "1M")
      (footprint "eagle-import:0603")
      (libsource (lib "eagle-import") (part "R-0603"))
    )
    (comp (ref "R90")
      (value "1k")
      (footprint "eagle-import:0603")
      (libsource (lib "eagle-import") (part "R-0603"))
    )
    (comp (ref "R91")
      (value "10k")
      (footprint "eagle-import:0603")
      (libsource (lib "eagle-import") (part "R-0603"))
    )
    (comp (ref "R92")
      (value "10R")
      (footprint "eagle-import:0603")
      (libsource (lib "eagle-import") (part "R-0603"))
    )
    (comp (ref "R93")
      (value "300R")
      (footprint "eagle-import:0603")
      (libsource (lib "eagle-import") (part "R-0603"))
    )
    (comp (ref "R94")
      (value "180k")
      (footprint "eagle-import:0603")
      (libsource (lib "eagle-import") (part "R-0603"))
    )
    (comp (ref "R95")
      (value "4M99")
      (footprint "eagle-import:0603")
      (libsource (lib "eagle-import") (part "R-0603"))
    )
    (comp (ref "R96")
      (value "560k")
      (footprint "eagle-import:0603")
      (libsource (lib "eagle-import") (part "R-0603"))
    )
    (comp (ref "R97")
      (value "180k")
      (footprint "eagle-import:0603")
      (libsource (lib "eagle-import") (part "R-0603"))
    )
    (comp (ref "R98")
      (value "4M99")
      (footprint "eagle-import:0603")
      (libsource (lib "eagle-import") (part "R-0603"))
    )
    (comp (ref "R99")
      (value "560k")
      (footprint "eagle-import:0603")
      (libsource (lib "eagle-import") (part "R-0603"))
    )
    (comp (ref "R100")
      (value "2k2")
      (footprint "eagle-import:0603")
      (libsource (lib "eagle-import") (part "R-0603"))
    )
    (comp (ref "R101")
      (value "2k2")
      (footprint "eagle-import:0603")
      (libsource (lib "eagle-import") (part "R-0603"))
    )
    (comp (ref "R102")
      (value "1k")
      (footprint "eagle-import:0603")
      (libsource (lib "eagle-import") (part "R-0603"))
    )
    (comp (ref "R103")
      (value "300R")
      (footprint "eagle-import:0603")
      (libsource (lib "eagle-import") (part "R-0603"))
    )
    (comp (ref "R105")
      (value "1R")
      (footprint "eagle-import:0805")
      (libsource (lib "eagle-import") (part "R-0805"))
    )
    (comp (ref "R106")
      (value "1R")
      (footprint "eagle-import:0805")
      (libsource (lib "eagle-import") (part "R-0805"))
    )
    (comp (ref "R128")
      (value "10k")
      (footprint "eagle-import:0603")
      (libsource (lib "eagle-import") (part "R-0603"))
    )
    (comp (ref "R129")
      (value "DNP/0R")
      (footprint "eagle-import:0603")
      (libsource (lib "eagle-import") (part "R-0603"))
    )
    (comp (ref "R130")
      (value "100k")
      (footprint "eagle-import:0603")
      (libsource (lib "eagle-import") (part "R-0603"))
    )
    (comp (ref "R132")
      (value "1M")
      (footprint "eagle-import:0603")
      (libsource (lib "eagle-import") (part "R-0603"))
    )
    (comp (ref "REF1")
      (value "REF")
      (footprint "eagle-import:REF")
      (libsource (lib "eagle-import") (part "REF"))
    )
    (comp (ref "REF2")
      (value "REF")
      (footprint "eagle-import:REF")
      (libsource (lib "eagle-import") (part "REF"))
    )
    (comp (ref "T1")
      (value "PIC-OUT")
      (footprint "eagle-import:TEMP-PAD")
      (libsource (lib "eagle-import") (part "PIC-OUT"))
    )
    (comp (ref "T3")
      (value "PIC-RPX")
      (footprint "eagle-import:TEMP-PAD")
      (libsource (lib "eagle-import") (part "PIC-RPX"))
    )
    (comp (ref "T5")
      (value "PIC-OUT")
      (footprint "eagle-import:TEMP-PAD")
      (libsource (lib "eagle-import") (part "PIC-OUT"))
    )
    (comp (ref "T7")
      (value "PIC-OUT")
      (footprint "eagle-import:TEMP-PAD")
      (libsource (lib "eagle-import") (part "PIC-OUT"))
    )
    (comp (ref "T13")
      (value "PIC-RPX")
      (footprint "eagle-import:TEMP-PAD")
      (libsource (lib "eagle-import") (part "PIC-RPX"))
    )
    (comp (ref "T14")
      (value "PIC-RPX")
      (footprint "eagle-import:TEMP-PAD")
      (libsource (lib "eagle-import") (part "PIC-RPX"))
    )
    (comp (ref "T15")
      (value "PIC-OUT")
      (footprint "eagle-import:TEMP-PAD")
      (libsource (lib "eagle-import") (part "PIC-OUT"))
    )
    (comp (ref "T27")
      (value "PIC-OUT")
      (footprint "eagle-import:TEMP-PAD")
      (libsource (lib "eagle-import") (part "PIC-OUT"))
    )
    (comp (ref "T32")
      (value "PIC-OUT")
      (footprint "eagle-import:TEMP-PAD")
      (libsource (lib "eagle-import") (part "PIC-OUT"))
    )
    (comp (ref "T33")
      (value "PIC-OUT")
      (footprint "eagle-import:TEMP-PAD")
      (libsource (lib "eagle-import") (part "PIC-OUT"))
    )
    (comp (ref "T36")
      (value "PIC-OUT")
      (footprint "eagle-import:TEMP-PAD")
      (libsource (lib "eagle-import") (part "PIC-OUT"))
    )
    (comp (ref "T37")
      (value "PIN-AN")
      (footprint "eagle-import:TEMP-PAD")
      (libsource (lib "eagle-import") (part "PIN-AN"))
    )
    (comp (ref "T38")
      (value "PIN-AN")
      (footprint "eagle-import:TEMP-PAD")
      (libsource (lib "eagle-import") (part "PIN-AN"))
    )
    (comp (ref "T39")
      (value "PIN-AN")
      (footprint "eagle-import:TEMP-PAD")
      (libsource (lib "eagle-import") (part "PIN-AN"))
    )
    (comp (ref "T45")
      (value "PIC-RPX")
      (footprint "eagle-import:TEMP-PAD")
      (libsource (lib "eagle-import") (part "PIC-RPX"))
    )
    (comp (ref "TP1")
      (value "DNP-TestPoint")
      (footprint "eagle-import:SMD_ROUND_1MM")
      (libsource (lib "eagle-import") (part "ROUND_SMD1MM"))
    )
    (comp (ref "TP2")
      (value "DNP-TestPoint")
      (footprint "eagle-import:TH_ROUND_14MM08MM")
      (libsource (lib "eagle-import") (part "ROUND_SMDTH1.4MM"))
    )
    (comp (ref "TP4")
      (value "DNP-TestPoint")
      (footprint "eagle-import:TH_ROUND_14MM08MM")
      (libsource (lib "eagle-import") (part "ROUND_SMDTH1.4MM"))
    )
    (comp (ref "X1")
      (value "8MHz-5x3.2mm")
      (footprint "eagle-import:7B")
      (libsource (lib "eagle-import") (part "XTAL-7B"))
    )
  )
  (nets
    (net (code "1") (name "+3.3V") (class "Default")
      (node (ref "C47") (pin "1") (pinfunction "1_1") (pintype "passive"))
      (node (ref "C48") (pin "1") (pinfunction "1_1") (pintype "passive"))
      (node (ref "C49") (pin "1") (pinfunction "1_1") (pintype "passive"))
      (node (ref "C50") (pin "1") (pinfunction "1_1") (pintype "passive"))
      (node (ref "C51") (pin "1") (pinfunction "1_1") (pintype "passive"))
      (node (ref "C52") (pin "1") (pinfunction "1_1") (pintype "passive"))
      (node (ref "C69") (pin "1") (pinfunction "1_1") (pintype "passive"))
      (node (ref "C70") (pin "1") (pinfunction "1_1") (pintype "passive"))
      (node (ref "C81") (pin "+") (pinfunction "+_+") (pintype "passive"))
      (node (ref "IC1") (pin "16") (pinfunction "VDD3_16") (pintype "input"))
      (node (ref "IC1") (pin "2") (pinfunction "VDD2_2") (pintype "input"))
      (node (ref "IC1") (pin "37") (pinfunction "VDD4_37") (pintype "input"))
      (node (ref "IC1") (pin "46") (pinfunction "VDD5_46") (pintype "input"))
      (node (ref "IC1") (pin "55") (pinfunction "VUSB3V3_55") (pintype "input"))
      (node (ref "IC1") (pin "62") (pinfunction "VDD6_62") (pintype "input"))
      (node (ref "IC1") (pin "86") (pinfunction "VDD1_86") (pintype "input"))
      (node (ref "J17") (pin "2") (pinfunction "2_2") (pintype "passive"))
      (node (ref "L13") (pin "1") (pinfunction "1_1") (pintype "passive"))
      (node (ref "R103") (pin "2") (pinfunction "2_2") (pintype "passive"))
      (node (ref "R105") (pin "2") (pinfunction "2_2") (pintype "passive"))
      (node (ref "R106") (pin "2") (pinfunction "2_2") (pintype "passive"))
      (node (ref "R129") (pin "1") (pinfunction "1_1") (pintype "passive"))
      (node (ref "R28") (pin "2") (pinfunction "2_2") (pintype "passive"))
      (node (ref "R65") (pin "1") (pinfunction "1_1") (pintype "passive"))
      (node (ref "R82") (pin "1") (pinfunction "1_1") (pintype "passive"))
      (node (ref "R91") (pin "2") (pinfunction "2_2") (pintype "passive"))
    )
    (net (code "2") (name "+3.3V{slash}1") (class "Default")
      (node (ref "C27") (pin "1") (pinfunction "1_1") (pintype "passive"))
      (node (ref "C28") (pin "1") (pinfunction "1_1") (pintype "passive"))
      (node (ref "IC11") (pin "2") (pinfunction "A1_2") (pintype "input"))
      (node (ref "IC11") (pin "8") (pinfunction "VCC_8") (pintype "input"))
      (node (ref "IC7") (pin "8") (pinfunction "VCC_8") (pintype "input"))
      (node (ref "IC9") (pin "3") (pinfunction "/WP_3") (pintype "input"))
      (node (ref "IC9") (pin "7") (pinfunction "/HOLD_7") (pintype "input"))
      (node (ref "IC9") (pin "8") (pinfunction "VCC_8") (pintype "input"))
      (node (ref "Q2") (pin "3") (pinfunction "D_3") (pintype "passive"))
      (node (ref "Q2") (pin "P2") (pinfunction "D1_P2") (pintype "passive"))
      (node (ref "R18") (pin "1") (pinfunction "1_1") (pintype "passive"))
      (node (ref "R25") (pin "2") (pinfunction "2_2") (pintype "passive"))
      (node (ref "R26") (pin "1") (pinfunction "1_1") (pintype "passive"))
      (node (ref "R27") (pin "1") (pinfunction "1_1") (pintype "passive"))
    )
    (net (code "3") (name "+3.3V{slash}2") (class "Default")
      (node (ref "C41") (pin "1") (pinfunction "1_1") (pintype "passive"))
      (node (ref "C86") (pin "+") (pinfunction "+_+") (pintype "passive"))
      (node (ref "IC12") (pin "8") (pinfunction "VCC_8") (pintype "input"))
      (node (ref "Q1") (pin "3") (pinfunction "D_3") (pintype "passive"))
      (node (ref "Q1") (pin "P2") (pinfunction "D1_P2") (pintype "passive"))
      (node (ref "R30") (pin "2") (pinfunction "2_2") (pintype "passive"))
      (node (ref "R34") (pin "1") (pinfunction "1_1") (pintype "passive"))
      (node (ref "R72") (pin "1") (pinfunction "1_1") (pintype "passive"))
      (node (ref "R73") (pin "2") (pinfunction "2_2") (pintype "passive"))
    )
    (net (code "4") (name "/A+") (class "Default")
      (node (ref "IC14") (pin "3") (pinfunction "3_3") (pintype "passive"))
      (node (ref "J3") (pin "4") (pinfunction "4_4") (pintype "passive"))
      (node (ref "J4") (pin "4") (pinfunction "4_4") (pintype "passive"))
      (node (ref "L8") (pin "2") (pinfunction "2_2") (pintype "passive"))
    )
    (net (code "5") (name "/A++") (class "Default")
      (node (ref "IC12") (pin "6") (pinfunction "A_6") (pintype "bidirectional"))
      (node (ref "L8") (pin "1") (pinfunction "1_1") (pintype "passive"))
      (node (ref "R32") (pin "2") (pinfunction "2_2") (pintype "passive"))
      (node (ref "R34") (pin "2") (pinfunction "2_2") (pintype "passive"))
    )
    (net (code "6") (name "/ACT-L-SENSE") (class "Default")
      (node (ref "R1") (pin "7") (pinfunction "2_7") (pintype "passive"))
      (node (ref "R1") (pin "8") (pinfunction "2_8") (pintype "passive"))
    )
    (net (code "7") (name "/ACT-L-SW") (class "Default")
      (node (ref "C44") (pin "1") (pinfunction "1_1") (pintype "passive"))
      (node (ref "J14") (pin "2") (pinfunction "2_2") (pintype "passive"))
      (node (ref "R1") (pin "1") (pinfunction "1_1") (pintype "passive"))
      (node (ref "R2") (pin "8") (pinfunction "2_8") (pintype "passive"))
    )
    (net (code "8") (name "/ACT-R-SENSE") (class "Default")
      (node (ref "R1") (pin "5") (pinfunction "2_5") (pintype "passive"))
      (node (ref "R1") (pin "6") (pinfunction "2_6") (pintype "passive"))
    )
    (net (code "9") (name "/ACT-R-SW") (class "Default")
      (node (ref "C3") (pin "1") (pinfunction "1_1") (pintype "passive"))
      (node (ref "J15") (pin "2") (pinfunction "2_2") (pintype "passive"))
      (node (ref "R1") (pin "3") (pinfunction "1_3") (pintype "passive"))
      (node (ref "R2") (pin "7") (pinfunction "2_7") (pintype "passive"))
    )
    (net (code "10") (name "/ACT_EN") (class "Default")
      (node (ref "R11") (pin "5") (pinfunction "2_5") (pintype "passive"))
      (node (ref "R11") (pin "6") (pinfunction "2_6") (pintype "passive"))
      (node (ref "R7") (pin "4") (pinfunction "1_4") (pintype "passive"))
    )
    (net (code "11") (name "/ACT_L+") (class "Default")
      (node (ref "IC2") (pin "31") (pinfunction "OUT1A_31") (pintype "output"))
      (node (ref "J14") (pin "1") (pinfunction "1_1") (pintype "passive"))
    )
    (net (code "12") (name "/ACT_L-") (class "Default")
      (node (ref "IC2") (pin "23") (pinfunction "OUT2A_23") (pintype "output"))
      (node (ref "J14") (pin "3") (pinfunction "3_3") (pintype "passive"))
    )
    (net (code "13") (name "/ACT_L1") (class "Default")
      (node (ref "IC2") (pin "27") (pinfunction "IN1_A_27") (pintype "input"))
      (node (ref "R10") (pin "5") (pinfunction "2_5") (pintype "passive"))
    )
    (net (code "14") (name "/ACT_L2") (class "Default")
      (node (ref "IC2") (pin "28") (pinfunction "IN2_A_28") (pintype "input"))
      (node (ref "R10") (pin "6") (pinfunction "2_6") (pintype "passive"))
    )
    (net (code "15") (name "/ACT_R+") (class "Default")
      (node (ref "IC2") (pin "9") (pinfunction "OUT1B_9") (pintype "output"))
      (node (ref "J15") (pin "1") (pinfunction "1_1") (pintype "passive"))
    )
    (net (code "16") (name "/ACT_R-") (class "Default")
      (node (ref "IC2") (pin "19") (pinfunction "OUT2B_19") (pintype "output"))
      (node (ref "J15") (pin "3") (pinfunction "3_3") (pintype "passive"))
    )
    (net (code "17") (name "/ACT_R1") (class "Default")
      (node (ref "IC2") (pin "13") (pinfunction "IN1_B_13") (pintype "input"))
      (node (ref "R10") (pin "7") (pinfunction "2_7") (pintype "passive"))
    )
    (net (code "18") (name "/ACT_R2") (class "Default")
      (node (ref "IC2") (pin "14") (pinfunction "IN2_B_14") (pintype "input"))
      (node (ref "R10") (pin "8") (pinfunction "2_8") (pintype "passive"))
    )
    (net (code "19") (name "/B-") (class "Default")
      (node (ref "IC14") (pin "2") (pinfunction "2_2") (pintype "passive"))
      (node (ref "J3") (pin "5") (pinfunction "5_5") (pintype "passive"))
      (node (ref "J4") (pin "5") (pinfunction "5_5") (pintype "passive"))
      (node (ref "L7") (pin "2") (pinfunction "2_2") (pintype "passive"))
    )
    (net (code "20") (name "/B--") (class "Default")
      (node (ref "IC12") (pin "7") (pinfunction "B_7") (pintype "bidirectional"))
      (node (ref "L7") (pin "1") (pinfunction "1_1") (pintype "passive"))
      (node (ref "R31") (pin "1") (pinfunction "1_1") (pintype "passive"))
      (node (ref "R32") (pin "1") (pinfunction "1_1") (pintype "passive"))
    )
    (net (code "21") (name "/CURR-SENSE") (class "Default")
      (node (ref "C66") (pin "1") (pinfunction "1_1") (pintype "passive"))
      (node (ref "IC1") (pin "14") (pinfunction "AN19/C2INC/RPG9/PMA2/RG9_14") (pintype "bidirectional"))
      (node (ref "O8") (pin "P$1") (pinfunction "TP_P$1") (pintype "passive"))
      (node (ref "R102") (pin "2") (pinfunction "2_2") (pintype "passive"))
      (node (ref "T39") (pin "P$1") (pinfunction "TP_P$1") (pintype "passive"))
    )
    (net (code "22") (name "/D+") (class "Default")
      (node (ref "IC1") (pin "57") (pinfunction "D+/RG2_57") (pintype "bidirectional"))
      (node (ref "IC15") (pin "3") (pinfunction "3_3") (pintype "passive"))
      (node (ref "J12") (pin "3_D+") (pinfunction "D+_3_D+") (pintype "bidirectional"))
    )
    (net (code "23") (name "/D-") (class "Default")
      (node (ref "IC1") (pin "56") (pinfunction "D-/RG3_56") (pintype "bidirectional"))
      (node (ref "IC15") (pin "2") (pinfunction "2_2") (pintype "passive"))
      (node (ref "J12") (pin "2_D-") (pinfunction "D-_2_D-") (pintype "bidirectional"))
    )
    (net (code "24") (name "/DOOR_L") (class "Default")
      (node (ref "R50") (pin "2") (pinfunction "1_2") (pintype "passive"))
      (node (ref "R50") (pin "3") (pinfunction "1_3") (pintype "passive"))
    )
    (net (code "25") (name "/DOOR_L_SW") (class "Default")
      (node (ref "C12") (pin "1") (pinfunction "1_1") (pintype "passive"))
      (node (ref "J14") (pin "4") (pinfunction "4_4") (pintype "passive"))
      (node (ref "R50") (pin "7") (pinfunction "2_7") (pintype "passive"))
      (node (ref "R6") (pin "2") (pinfunction "2_2") (pintype "passive"))
    )
    (net (code "26") (name "/DOOR_ON") (class "Default")
      (node (ref "Q3") (pin "5") (pinfunction "Q1G_5") (pintype "input"))
      (node (ref "R9") (pin "7") (pinfunction "2_7") (pintype "passive"))
    )
    (net (code "27") (name "/DOOR_R") (class "Default")
      (node (ref "R50") (pin "1") (pinfunction "1_1") (pintype "passive"))
      (node (ref "R50") (pin "4") (pinfunction "1_4") (pintype "passive"))
    )
    (net (code "28") (name "/DOOR_R_SW") (class "Default")
      (node (ref "C4") (pin "1") (pinfunction "1_1") (pintype "passive"))
      (node (ref "J15") (pin "4") (pinfunction "4_4") (pintype "passive"))
      (node (ref "R50") (pin "8") (pinfunction "2_8") (pintype "passive"))
      (node (ref "R8") (pin "2") (pinfunction "2_2") (pintype "passive"))
    )
    (net (code "29") (name "/LAN-CTL") (class "Default")
      (node (ref "IC1") (pin "84") (pinfunction "PMD15/RD7_84") (pintype "bidirectional"))
      (node (ref "IC12") (pin "2") (pinfunction "/RE_2") (pintype "input"))
      (node (ref "IC12") (pin "3") (pinfunction "DE_3") (pintype "input"))
      (node (ref "O31") (pin "P$1") (pinfunction "TP_P$1") (pintype "passive"))
      (node (ref "R71") (pin "1") (pinfunction "1_1") (pintype "passive"))
      (node (ref "T15") (pin "P$1") (pinfunction "TP_P$1") (pintype "passive"))
    )
    (net (code "30") (name "/LAN-RX") (class "Default")
      (node (ref "IC1") (pin "88") (pinfunction "RPF1/PMD10/RF1_88") (pintype "bidirectional"))
      (node (ref "IC12") (pin "1") (pinfunction "R_1") (pintype "output"))
      (node (ref "O29") (pin "P$1") (pinfunction "TP_P$1") (pintype "passive"))
      (node (ref "R72") (pin "2") (pinfunction "2_2") (pintype "passive"))
      (node (ref "T13") (pin "P$1") (pinfunction "TP_P$1") (pintype "passive"))
    )
    (net (code "31") (name "/LAN-TX") (class "Default")
      (node (ref "IC1") (pin "87") (pinfunction "RPF0/PMD11/RF0_87") (pintype "bidirectional"))
      (node (ref "IC12") (pin "4") (pinfunction "D_4") (pintype "input"))
      (node (ref "O30") (pin "P$1") (pinfunction "TP_P$1") (pintype "passive"))
      (node (ref "R73") (pin "1") (pinfunction "1_1") (pintype "passive"))
      (node (ref "T14") (pin "P$1") (pinfunction "TP_P$1") (pintype "passive"))
    )
    (net (code "32") (name "/LED-PIC") (class "Default")
      (node (ref "IC1") (pin "1") (pinfunction "RG15_1") (pintype "bidirectional"))
      (node (ref "O1") (pin "P$1") (pinfunction "TP_P$1") (pintype "passive"))
      (node (ref "R29") (pin "1") (pinfunction "1_1") (pintype "passive"))
      (node (ref "T36") (pin "P$1") (pinfunction "TP_P$1") (pintype "passive"))
      (node (ref "TP4") (pin "P$1") (pinfunction "TP_P$1") (pintype "passive"))
    )
    (net (code "33") (name "/PGC") (class "Default")
      (node (ref "IC1") (pin "24") (pinfunction "PGEC1/AN1/RPB1/CTED12/RB1_24") (pintype "bidirectional"))
      (node (ref "J17") (pin "5") (pinfunction "5_5") (pintype "passive"))
    )
    (net (code "34") (name "/PGD") (class "Default")
      (node (ref "IC1") (pin "25") (pinfunction "PGED1/AN0/RPB0/RB0_25") (pintype "bidirectional"))
      (node (ref "J17") (pin "4") (pinfunction "4_4") (pintype "passive"))
      (node (ref "R130") (pin "2") (pinfunction "2_2") (pintype "passive"))
    )
    (net (code "35") (name "/POWER-GOOD") (class "Default")
      (node (ref "IC6") (pin "4") (pinfunction "OUT_4") (pintype "output"))
      (node (ref "R130") (pin "1") (pinfunction "1_1") (pintype "passive"))
      (node (ref "T45") (pin "P$1") (pinfunction "TP_P$1") (pintype "passive"))
      (node (ref "TP2") (pin "P$1") (pinfunction "TP_P$1") (pintype "passive"))
    )
    (net (code "36") (name "/REF-EN") (class "Default")
      (node (ref "IC1") (pin "28") (pinfunction "VREF-/CVREF-/PMA7/RA9_28") (pintype "bidirectional"))
      (node (ref "R93") (pin "1") (pinfunction "1_1") (pintype "passive"))
    )
    (net (code "37") (name "/REF2,5V") (class "Default")
      (node (ref "C57") (pin "1") (pinfunction "1_1") (pintype "passive"))
      (node (ref "IC1") (pin "29") (pinfunction "VREF+/CVREF+/PMA6/RA10_29") (pintype "bidirectional"))
      (node (ref "IC13") (pin "2") (pinfunction "VOUT_2") (pintype "bidirectional"))
    )
    (net (code "38") (name "/SCL1-EEPROM") (class "Default")
      (node (ref "IC1") (pin "66") (pinfunction "SCL1/RPA14/RA14_66") (pintype "bidirectional"))
      (node (ref "IC11") (pin "6") (pinfunction "SCL_6") (pintype "input"))
      (node (ref "IC7") (pin "6") (pinfunction "SCL_6") (pintype "input"))
      (node (ref "R26") (pin "2") (pinfunction "2_2") (pintype "passive"))
    )
    (net (code "39") (name "/SCLK2-SPI") (class "Default")
      (node (ref "IC1") (pin "10") (pinfunction "AN16/C1IND/RPG6/SCK2/PMA5/RG6_10") (pintype "bidirectional"))
      (node (ref "IC9") (pin "6") (pinfunction "C_6") (pintype "input"))
    )
    (net (code "40") (name "/SD-CS") (class "Default")
      (node (ref "IC1") (pin "9") (pinfunction "RPC4/CTED7/RC4_9") (pintype "bidirectional"))
      (node (ref "O5") (pin "P$1") (pinfunction "TP_P$1") (pintype "passive"))
    )
    (net (code "41") (name "/SDA1-EEPROM") (class "Default")
      (node (ref "IC1") (pin "67") (pinfunction "SDA1/RPA15/RA15_67") (pintype "bidirectional"))
      (node (ref "IC11") (pin "5") (pinfunction "SDA_5") (pintype "bidirectional"))
      (node (ref "IC7") (pin "5") (pinfunction "SDA_5") (pintype "bidirectional"))
      (node (ref "R27") (pin "2") (pinfunction "2_2") (pintype "passive"))
    )
    (net (code "42") (name "/SDI2-MISO") (class "Default")
      (node (ref "IC1") (pin "22") (pinfunction "PGED3/AN3/C2INA/RPB3/RB3_22") (pintype "bidirectional"))
      (node (ref "IC9") (pin "2") (pinfunction "Q_2") (pintype "bidirectional"))
      (node (ref "O13") (pin "P$1") (pinfunction "TP_P$1") (pintype "passive"))
    )
    (net (code "43") (name "/SDO2-MOSI") (class "Default")
      (node (ref "IC1") (pin "20") (pinfunction "AN5/C1INA/RPB5/RB5_20") (pintype "bidirectional"))
      (node (ref "IC9") (pin "5") (pinfunction "D_5") (pintype "input"))
      (node (ref "O12") (pin "P$1") (pinfunction "TP_P$1") (pintype "passive"))
    )
    (net (code "44") (name "/VACT-ON") (class "Default")
      (node (ref "Q6") (pin "2") (pinfunction "G_2") (pintype "passive"))
      (node (ref "R12") (pin "1") (pinfunction "1_1") (pintype "passive"))
      (node (ref "T1") (pin "P$1") (pinfunction "TP_P$1") (pintype "passive"))
    )
    (net (code "45") (name "/VBAT-LAN") (class "Default")
      (node (ref "D3") (pin "C") (pinfunction "C_C") (pintype "passive"))
      (node (ref "J3") (pin "1") (pinfunction "1_1") (pintype "passive"))
      (node (ref "J3") (pin "3") (pinfunction "3_3") (pintype "passive"))
      (node (ref "J4") (pin "1") (pinfunction "1_1") (pintype "passive"))
      (node (ref "J4") (pin "3") (pinfunction "3_3") (pintype "passive"))
      (node (ref "L11") (pin "2") (pinfunction "2_2") (pintype "passive"))
    )
    (net (code "46") (name "/VBAT-LAN-F") (class "Default")
      (node (ref "C33") (pin "1") (pinfunction "1_1") (pintype "passive"))
      (node (ref "C34") (pin "1") (pinfunction "1_1") (pintype "passive"))
      (node (ref "D6") (pin "K") (pinfunction "K_K") (pintype "passive"))
      (node (ref "L11") (pin "1") (pinfunction "1_1") (pintype "passive"))
      (node (ref "Q5") (pin "2") (pinfunction "S_2") (pintype "passive"))
      (node (ref "Q5") (pin "5") (pinfunction "S_5") (pintype "passive"))
      (node (ref "R132") (pin "1") (pinfunction "1_1") (pintype "passive"))
      (node (ref "R36") (pin "2") (pinfunction "2_2") (pintype "passive"))
      (node (ref "R38") (pin "2") (pinfunction "2_2") (pintype "passive"))
      (node (ref "R42") (pin "1") (pinfunction "1_1") (pintype "passive"))
      (node (ref "R45") (pin "1") (pinfunction "1_1") (pintype "passive"))
      (node (ref "R94") (pin "1") (pinfunction "1_1") (pintype "passive"))
    )
    (net (code "47") (name "/VBAT-ON") (class "Default")
      (node (ref "IC1") (pin "52") (pinfunction "RPF2/RF2_52") (pintype "bidirectional"))
      (node (ref "O42") (pin "P$1") (pinfunction "TP_P$1") (pintype "passive"))
      (node (ref "Q4") (pin "2") (pinfunction "G_2") (pintype "passive"))
      (node (ref "R132") (pin "2") (pinfunction "2_2") (pintype "passive"))
      (node (ref "R41") (pin "1") (pinfunction "1_1") (pintype "passive"))
      (node (ref "T5") (pin "P$1") (pinfunction "TP_P$1") (pintype "passive"))
    )
    (net (code "48") (name "/VBAT-SENSE") (class "Default")
      (node (ref "C64") (pin "1") (pinfunction "1_1") (pintype "passive"))
      (node (ref "IC1") (pin "26") (pinfunction "PGEC2/AN6/RPB6/RB6_26") (pintype "bidirectional"))
      (node (ref "O15") (pin "P$1") (pinfunction "TP_P$1") (pintype "passive"))
      (node (ref "R100") (pin "1") (pinfunction "1_1") (pintype "passive"))
      (node (ref "T37") (pin "P$1") (pinfunction "TP_P$1") (pintype "passive"))
    )
    (net (code "49") (name "/VBATLAN-SENSE") (class "Default")
      (node (ref "C36") (pin "1") (pinfunction "1_1") (pintype "passive"))
      (node (ref "IC1") (pin "27") (pinfunction "PGED2/AN7/RPB7/CTED3/RB7_27") (pintype "bidirectional"))
      (node (ref "O16") (pin "P$1") (pinfunction "TP_P$1") (pintype "passive"))
      (node (ref "R101") (pin "1") (pinfunction "1_1") (pintype "passive"))
      (node (ref "T38") (pin "P$1") (pinfunction "TP_P$1") (pintype "passive"))
    )
    (net (code "50") (name "/VBUS") (class "Default")
      (node (ref "IC1") (pin "54") (pinfunction "VBUS_54") (pintype "input"))
      (node (ref "R128") (pin "2") (pinfunction "2_2") (pintype "passive"))
    )
    (net (code "51") (name "/VPS-ON") (class "Default")
      (node (ref "IC1") (pin "53") (pinfunction "RPF8/RF8_53") (pintype "bidirectional"))
      (node (ref "O41") (pin "P$1") (pinfunction "TP_P$1") (pintype "passive"))
      (node (ref "Q4") (pin "5") (pinfunction "G_5") (pintype "passive"))
      (node (ref "R44") (pin "1") (pinfunction "1_1") (pintype "passive"))
      (node (ref "T7") (pin "P$1") (pinfunction "TP_P$1") (pintype "passive"))
    )
    (net (code "52") (name "/VPS-PWR") (class "Default")
      (node (ref "D4") (pin "C") (pinfunction "C_C") (pintype "passive"))
      (node (ref "J3") (pin "6") (pinfunction "6_6") (pintype "passive"))
      (node (ref "J4") (pin "6") (pinfunction "6_6") (pintype "passive"))
      (node (ref "L10") (pin "2") (pinfunction "2_2") (pintype "passive"))
    )
    (net (code "53") (name "/VPS-PWR-F") (class "Default")
      (node (ref "L10") (pin "1") (pinfunction "1_1") (pintype "passive"))
      (node (ref "Q5") (pin "4") (pinfunction "D_4") (pintype "passive"))
      (node (ref "R23") (pin "2") (pinfunction "2_2") (pintype "passive"))
    )
    (net (code "54") (name "/VPS-SENSE") (class "Default")
      (node (ref "C65") (pin "1") (pinfunction "1_1") (pintype "passive"))
      (node (ref "IC1") (pin "12") (pinfunction "AN18/C2IND/RPG8/PMA3/RG8_12") (pintype "bidirectional"))
      (node (ref "O7") (pin "P$1") (pinfunction "TP_P$1") (pintype "passive"))
      (node (ref "R48") (pin "2") (pinfunction "2_2") (pintype "passive"))
      (node (ref "R49") (pin "1") (pinfunction "1_1") (pintype "passive"))
      (node (ref "T3") (pin "P$1") (pinfunction "TP_P$1") (pintype "passive"))
    )
    (net (code "55") (name "/{slash}3.3V1PWRON") (class "Default")
      (node (ref "IC1") (pin "21") (pinfunction "AN4/C1INB/USBOEN/RB4_21") (pintype "bidirectional"))
      (node (ref "O44") (pin "P$1") (pinfunction "TP_P$1") (pintype "passive"))
      (node (ref "R24") (pin "2") (pinfunction "2_2") (pintype "passive"))
      (node (ref "T32") (pin "P$1") (pinfunction "TP_P$1") (pintype "passive"))
    )
    (net (code "56") (name "/{slash}3.3V2PWRON") (class "Default")
      (node (ref "IC1") (pin "96") (pinfunction "TRD1/RG12_96") (pintype "bidirectional"))
      (node (ref "O23") (pin "P$1") (pinfunction "TP_P$1") (pintype "passive"))
      (node (ref "R75") (pin "2") (pinfunction "2_2") (pintype "passive"))
      (node (ref "T33") (pin "P$1") (pinfunction "TP_P$1") (pintype "passive"))
    )
    (net (code "57") (name "/{slash}FMEM1-CS") (class "Default")
      (node (ref "IC1") (pin "11") (pinfunction "AN17/C1INC/RPG7/PMA4/RG7_11") (pintype "bidirectional"))
      (node (ref "IC9") (pin "1") (pinfunction "/S_1") (pintype "input"))
      (node (ref "O6") (pin "P$1") (pinfunction "TP_P$1") (pintype "passive"))
      (node (ref "R25") (pin "1") (pinfunction "1_1") (pintype "passive"))
      (node (ref "T27") (pin "P$1") (pinfunction "TP_P$1") (pintype "passive"))
    )
    (net (code "58") (name "/{slash}MCLR") (class "Default")
      (node (ref "IC1") (pin "13") (pinfunction "~{MCLR}_13") (pintype "input"))
      (node (ref "J17") (pin "1") (pinfunction "1_1") (pintype "passive"))
      (node (ref "R90") (pin "2") (pinfunction "2_2") (pintype "passive"))
    )
    (net (code "59") (name "DGND") (class "Default")
      (node (ref "C22") (pin "2") (pinfunction "2_2") (pintype "passive"))
      (node (ref "C23") (pin "2") (pinfunction "2_2") (pintype "passive"))
      (node (ref "C24") (pin "1") (pinfunction "1_1") (pintype "passive"))
      (node (ref "C27") (pin "2") (pinfunction "2_2") (pintype "passive"))
      (node (ref "C28") (pin "2") (pinfunction "2_2") (pintype "passive"))
      (node (ref "C29") (pin "2") (pinfunction "2_2") (pintype "passive"))
      (node (ref "C30") (pin "2") (pinfunction "2_2") (pintype "passive"))
      (node (ref "C31") (pin "-") (pinfunction "-_-") (pintype "passive"))
      (node (ref "C35") (pin "2") (pinfunction "2_2") (pintype "passive"))
      (node (ref "C36") (pin "2") (pinfunction "2_2") (pintype "passive"))
      (node (ref "C40") (pin "2") (pinfunction "2_2") (pintype "passive"))
      (node (ref "C41") (pin "2") (pinfunction "2_2") (pintype "passive"))
      (node (ref "C47") (pin "2") (pinfunction "2_2") (pintype "passive"))
      (node (ref "C48") (pin "2") (pinfunction "2_2") (pintype "passive"))
      (node (ref "C49") (pin "2") (pinfunction "2_2") (pintype "passive"))
      (node (ref "C50") (pin "2") (pinfunction "2_2") (pintype "passive"))
      (node (ref "C51") (pin "2") (pinfunction "2_2") (pintype "passive"))
      (node (ref "C52") (pin "2") (pinfunction "2_2") (pintype "passive"))
      (node (ref "C53") (pin "2") (pinfunction "2_2") (pintype "passive"))
      (node (ref "C54") (pin "-") (pinfunction "-_-") (pintype "passive"))
      (node (ref "C55") (pin "2") (pinfunction "2_2") (pintype "passive"))
      (node (ref "C56") (pin "-") (pinfunction "-_-") (pintype "passive"))
      (node (ref "C57") (pin "2") (pinfunction "2_2") (pintype "passive"))
      (node (ref "C58") (pin "2") (pinfunction "2_2") (pintype "passive"))
      (node (ref "C59") (pin "2") (pinfunction "2_2") (pintype "passive"))
      (node (ref "C60") (pin "2") (pinfunction "2_2") (pintype "passive"))
      (node (ref "C61") (pin "2") (pinfunction "2_2") (pintype "passive"))
      (node (ref "C62") (pin "2") (pinfunction "2_2") (pintype "passive"))
      (node (ref "C63") (pin "2") (pinfunction "2_2") (pintype "passive"))
      (node (ref "C64") (pin "2") (pinfunction "2_2") (pintype "passive"))
      (node (ref "C65") (pin "2") (pinfunction "2_2") (pintype "passive"))
      (node (ref "C66") (pin "2") (pinfunction "2_2") (pintype "passive"))
      (node (ref "C67") (pin "2") (pinfunction "2_2") (pintype "passive"))
      (node (ref "C81") (pin "-") (pinfunction "-_-") (pintype "passive"))
      (node (ref "C83") (pin "2") (pinfunction "2_2") (pintype "passive"))
      (node (ref "C84") (pin "2") (pinfunction "2_2") (pintype "passive"))
      (node (ref "C85") (pin "2") (pinfunction "2_2") (pintype "passive"))
      (node (ref "C86") (pin "-") (pinfunction "-_-") (pintype "passive"))
      (node (ref "C88") (pin "2") (pinfunction "2_2") (pintype "passive"))
      (node (ref "D2") (pin "-") (pinfunction "A_-") (pintype "passive"))
      (node (ref "D5") (pin "K") (pinfunction "K_K") (pintype "passive"))
      (node (ref "D7") (pin "A") (pinfunction "A_A") (pintype "passive"))
      (node (ref "IC1") (pin "15") (pinfunction "VSS2_15") (pintype "input"))
      (node (ref "IC1") (pin "31") (pinfunction "AVSS_31") (pintype "input"))
      (node (ref "IC1") (pin "36") (pinfunction "VSS3_36") (pintype "input"))
      (node (ref "IC1") (pin "45") (pinfunction "VSS4_45") (pintype "input"))
      (node (ref "IC1") (pin "65") (pinfunction "VSS5_65") (pintype "input"))
      (node (ref "IC1") (pin "75") (pinfunction "VSS1_75") (pintype "input"))
      (node (ref "IC10") (pin "1") (pinfunction "GND_1") (pintype "input"))
      (node (ref "IC10") (pin "2") (pinfunction "GND1_2") (pintype "input"))
      (node (ref "IC11") (pin "1") (pinfunction "A0_1") (pintype "input"))
      (node (ref "IC11") (pin "3") (pinfunction "A2_3") (pintype "input"))
      (node (ref "IC11") (pin "4") (pinfunction "GND_4") (pintype "input"))
      (node (ref "IC12") (pin "5") (pinfunction "GND_5") (pintype "input"))
      (node (ref "IC13") (pin "3") (pinfunction "GND_3") (pintype "bidirectional"))
      (node (ref "IC15") (pin "1") (pinfunction "1_1") (pintype "input"))
      (node (ref "IC16") (pin "4") (pinfunction "V-_4") (pintype "input"))
      (node (ref "IC6") (pin "2") (pinfunction "GND_2") (pintype "input"))
      (node (ref "IC7") (pin "1") (pinfunction "A0_1") (pintype "input"))
      (node (ref "IC7") (pin "2") (pinfunction "A1_2") (pintype "input"))
      (node (ref "IC7") (pin "3") (pinfunction "A2_3") (pintype "input"))
      (node (ref "IC7") (pin "4") (pinfunction "GND_4") (pintype "input"))
      (node (ref "IC7") (pin "7") (pinfunction "WP_7") (pintype "input"))
      (node (ref "IC8") (pin "10") (pinfunction "SYNC_10") (pintype "bidirectional"))
      (node (ref "IC8") (pin "EP") (pinfunction "GND_EP") (pintype "bidirectional"))
      (node (ref "IC9") (pin "4") (pinfunction "GND_4") (pintype "input"))
      (node (ref "J12") (pin "4_GND") (pinfunction "GND_4_GND") (pintype "bidirectional"))
      (node (ref "J12") (pin "SH1") (pinfunction "GND_SH1_SH1") (pintype "bidirectional"))
      (node (ref "J12") (pin "SH2") (pinfunction "GND_SH2_SH2") (pintype "bidirectional"))
      (node (ref "J17") (pin "3") (pinfunction "3_3") (pintype "passive"))
      (node (ref "L12") (pin "1") (pinfunction "1_1") (pintype "passive"))
      (node (ref "L2") (pin "2") (pinfunction "2_2") (pintype "passive"))
      (node (ref "PCB1") (pin "PAD_GND_1") (pinfunction "PAD_GND_1_PAD_GND_1") (pintype "bidirectional"))
      (node (ref "PCB1") (pin "PAD_GND_2") (pinfunction "PAD_GND_2_PAD_GND_2") (pintype "bidirectional"))
      (node (ref "PCB1") (pin "PAD_GND_3") (pinfunction "PAD_GND_3_PAD_GND_3") (pintype "bidirectional"))
      (node (ref "PCB1") (pin "PAD_GND_4") (pinfunction "PAD_GND_4_PAD_GND_4") (pintype "bidirectional"))
      (node (ref "R12") (pin "2") (pinfunction "2_2") (pintype "passive"))
      (node (ref "R14") (pin "1") (pinfunction "1_1") (pintype "passive"))
      (node (ref "R17") (pin "2") (pinfunction "2_2") (pintype "passive"))
      (node (ref "R19") (pin "2") (pinfunction "2_2") (pintype "passive"))
      (node (ref "R21") (pin "2") (pinfunction "2_2") (pintype "passive"))
      (node (ref "R31") (pin "2") (pinfunction "2_2") (pintype "passive"))
      (node (ref "R40") (pin "1") (pinfunction "1_1") (pintype "passive"))
      (node (ref "R41") (pin "2") (pinfunction "2_2") (pintype "passive"))
      (node (ref "R43") (pin "1") (pinfunction "1_1") (pintype "passive"))
      (node (ref "R44") (pin "2") (pinfunction "2_2") (pintype "passive"))
      (node (ref "R46") (pin "1") (pinfunction "1_1") (pintype "passive"))
      (node (ref "R48") (pin "1") (pinfunction "1_1") (pintype "passive"))
      (node (ref "R71") (pin "2") (pinfunction "2_2") (pintype "passive"))
      (node (ref "R96") (pin "2") (pinfunction "2_2") (pintype "passive"))
      (node (ref "R99") (pin "2") (pinfunction "2_2") (pintype "passive"))
    )
    (net (code "60") (name "Net-(C24-Pad2)") (class "Default")
      (node (ref "C24") (pin "2") (pinfunction "2_2") (pintype "passive"))
      (node (ref "R77") (pin "2") (pinfunction "2_2") (pintype "passive"))
    )
    (net (code "61") (name "Net-(C39-Pad1)") (class "Default")
      (node (ref "C39") (pin "1") (pinfunction "1_1") (pintype "passive"))
      (node (ref "IC14") (pin "4") (pinfunction "4_4") (pintype "input"))
      (node (ref "R30") (pin "1") (pinfunction "1_1") (pintype "passive"))
    )
    (net (code "62") (name "Net-(C39-Pad2)") (class "Default")
      (node (ref "C39") (pin "2") (pinfunction "2_2") (pintype "passive"))
      (node (ref "D3") (pin "A") (pinfunction "A_A") (pintype "passive"))
      (node (ref "D4") (pin "A") (pinfunction "A_A") (pintype "passive"))
      (node (ref "IC14") (pin "1") (pinfunction "1_1") (pintype "input"))
      (node (ref "J3") (pin "2") (pinfunction "2_2") (pintype "passive"))
      (node (ref "J3") (pin "7") (pinfunction "7_7") (pintype "passive"))
      (node (ref "J3") (pin "8") (pinfunction "8_8") (pintype "passive"))
      (node (ref "J4") (pin "2") (pinfunction "2_2") (pintype "passive"))
      (node (ref "J4") (pin "7") (pinfunction "7_7") (pintype "passive"))
      (node (ref "J4") (pin "8") (pinfunction "8_8") (pintype "passive"))
      (node (ref "L12") (pin "2") (pinfunction "2_2") (pintype "passive"))
    )
    (net (code "63") (name "Net-(C40-Pad1)") (class "Default")
      (node (ref "C40") (pin "1") (pinfunction "1_1") (pintype "passive"))
      (node (ref "R90") (pin "1") (pinfunction "1_1") (pintype "passive"))
      (node (ref "R91") (pin "1") (pinfunction "1_1") (pintype "passive"))
    )
    (net (code "64") (name "Net-(D1-K)") (class "Default")
      (node (ref "C37") (pin "2") (pinfunction "2_2") (pintype "passive"))
      (node (ref "D1") (pin "2") (pinfunction "K_2") (pintype "passive"))
      (node (ref "IC2") (pin "17") (pinfunction "VBOOT_17") (pintype "input"))
    )
    (net (code "65") (name "Net-(D1-KA)") (class "Default")
      (node (ref "C2") (pin "1") (pinfunction "1_1") (pintype "passive"))
      (node (ref "D1") (pin "3") (pinfunction "KA_3") (pintype "passive"))
    )
    (net (code "66") (name "Net-(D2-C)") (class "Default")
      (node (ref "C26") (pin "1") (pinfunction "1_1") (pintype "passive"))
      (node (ref "C30") (pin "1") (pinfunction "1_1") (pintype "passive"))
      (node (ref "C31") (pin "+") (pinfunction "+_+") (pintype "passive"))
      (node (ref "D2") (pin "+") (pinfunction "C_+") (pintype "passive"))
      (node (ref "IC8") (pin "1") (pinfunction "BD_1") (pintype "bidirectional"))
      (node (ref "L9") (pin "2") (pinfunction "2_2") (pintype "passive"))
      (node (ref "R129") (pin "2") (pinfunction "2_2") (pintype "passive"))
      (node (ref "R20") (pin "1") (pinfunction "1_1") (pintype "passive"))
    )
    (net (code "67") (name "Net-(D5-PadA)") (class "Default")
      (node (ref "D5") (pin "A") (pinfunction "A_A") (pintype "passive"))
      (node (ref "R29") (pin "2") (pinfunction "2_2") (pintype "passive"))
    )
    (net (code "68") (name "Net-(D9-C)") (class "Default")
      (node (ref "D9") (pin "3") (pinfunction "C_3") (pintype "passive"))
      (node (ref "R2") (pin "1") (pinfunction "1_1") (pintype "passive"))
      (node (ref "R2") (pin "2") (pinfunction "1_2") (pintype "passive"))
      (node (ref "R7") (pin "6") (pinfunction "2_6") (pintype "passive"))
    )
    (net (code "69") (name "Net-(IC1-AVDD)") (class "Default")
      (node (ref "C55") (pin "1") (pinfunction "1_1") (pintype "passive"))
      (node (ref "C56") (pin "+") (pinfunction "+_+") (pintype "passive"))
      (node (ref "C88") (pin "1") (pinfunction "1_1") (pintype "passive"))
      (node (ref "IC1") (pin "30") (pinfunction "AVDD_30") (pintype "input"))
      (node (ref "R92") (pin "2") (pinfunction "2_2") (pintype "passive"))
    )
    (net (code "70") (name "Net-(IC1-CLKI{slash}RC12{slash}OSC1)") (class "Default")
      (node (ref "C60") (pin "1") (pinfunction "1_1") (pintype "passive"))
      (node (ref "IC1") (pin "63") (pinfunction "CLKI/RC12/OSC1_63") (pintype "bidirectional"))
      (node (ref "X1") (pin "3") (pinfunction "2_3") (pintype "passive"))
    )
    (net (code "71") (name "Net-(IC1-CLKO{slash}RC15{slash}OSC2)") (class "Default")
      (node (ref "C61") (pin "1") (pinfunction "1_1") (pintype "passive"))
      (node (ref "IC1") (pin "64") (pinfunction "CLKO/RC15/OSC2_64") (pintype "bidirectional"))
      (node (ref "X1") (pin "1") (pinfunction "1_1") (pintype "passive"))
    )
    (net (code "72") (name "Net-(IC1-VCAP)") (class "Default")
      (node (ref "C53") (pin "1") (pinfunction "1_1") (pintype "passive"))
      (node (ref "C54") (pin "+") (pinfunction "+_+") (pintype "passive"))
      (node (ref "IC1") (pin "85") (pinfunction "VCAP_85") (pintype "input"))
    )
    (net (code "73") (name "Net-(IC2-EN_A)") (class "Default")
      (node (ref "C5") (pin "1") (pinfunction "1_1") (pintype "passive"))
      (node (ref "IC2") (pin "25") (pinfunction "EN_A_25") (pintype "input"))
      (node (ref "R11") (pin "4") (pinfunction "1_4") (pintype "passive"))
    )
    (net (code "74") (name "Net-(IC2-EN_B)") (class "Default")
      (node (ref "C43") (pin "1") (pinfunction "1_1") (pintype "passive"))
      (node (ref "IC2") (pin "16") (pinfunction "EN_B_16") (pintype "input"))
      (node (ref "R11") (pin "3") (pinfunction "1_3") (pintype "passive"))
    )
    (net (code "75") (name "Net-(IC2-RCA)") (class "Default")
      (node (ref "C7") (pin "1") (pinfunction "1_1") (pintype "passive"))
      (node (ref "IC2") (pin "30") (pinfunction "RCA_30") (pintype "input"))
      (node (ref "R11") (pin "2") (pinfunction "1_2") (pintype "passive"))
    )
    (net (code "76") (name "Net-(IC2-RCB)") (class "Default")
      (node (ref "C6") (pin "1") (pinfunction "1_1") (pintype "passive"))
      (node (ref "IC2") (pin "11") (pinfunction "RCB_11") (pintype "input"))
      (node (ref "R11") (pin "1") (pinfunction "1_1") (pintype "passive"))
    )
    (net (code "77") (name "Net-(IC2-SENSE_A)") (class "Default")
      (node (ref "IC2") (pin "29") (pinfunction "SENSE_A_29") (pintype "input"))
      (node (ref "R5") (pin "2") (pinfunction "2_2") (pintype "passive"))
    )
    (net (code "78") (name "Net-(IC2-SENSE_B)") (class "Default")
      (node (ref "IC2") (pin "12") (pinfunction "SENSE_B_12") (pintype "input"))
      (node (ref "R4") (pin "2") (pinfunction "2_2") (pintype "passive"))
    )
    (net (code "79") (name "Net-(IC2-VCP)") (class "Default")
      (node (ref "C2") (pin "2") (pinfunction "2_2") (pintype "passive"))
      (node (ref "IC2") (pin "24") (pinfunction "VCP_24") (pintype "input"))
    )
    (net (code "80") (name "Net-(IC2-VREF_A)") (class "Default")
      (node (ref "IC2") (pin "15") (pinfunction "VREF_B_15") (pintype "input"))
      (node (ref "IC2") (pin "26") (pinfunction "VREF_A_26") (pintype "input"))
      (node (ref "R3") (pin "2") (pinfunction "2_2") (pintype "passive"))
      (node (ref "R7") (pin "5") (pinfunction "2_5") (pintype "passive"))
    )
    (net (code "81") (name "Net-(IC6-HTH)") (class "Default")
      (node (ref "IC6") (pin "1") (pinfunction "HTH_1") (pintype "input"))
      (node (ref "R46") (pin "2") (pinfunction "2_2") (pintype "passive"))
      (node (ref "R47") (pin "1") (pinfunction "1_1") (pintype "passive"))
    )
    (net (code "82") (name "Net-(IC6-LTH)") (class "Default")
      (node (ref "IC6") (pin "3") (pinfunction "LTH_3") (pintype "input"))
      (node (ref "R33") (pin "1") (pinfunction "1_1") (pintype "passive"))
      (node (ref "R47") (pin "2") (pinfunction "2_2") (pintype "passive"))
    )
    (net (code "83") (name "Net-(IC6-VDD)") (class "Default")
      (node (ref "C35") (pin "1") (pinfunction "1_1") (pintype "passive"))
      (node (ref "IC6") (pin "5") (pinfunction "VDD_5") (pintype "input"))
      (node (ref "R28") (pin "1") (pinfunction "1_1") (pintype "passive"))
    )
    (net (code "84") (name "Net-(IC8-BOOST)") (class "Default")
      (node (ref "C25") (pin "2") (pinfunction "2_2") (pintype "passive"))
      (node (ref "IC8") (pin "2") (pinfunction "BOOST_2") (pintype "bidirectional"))
    )
    (net (code "85") (name "Net-(IC8-EN)") (class "Default")
      (node (ref "IC8") (pin "5") (pinfunction "EN_5") (pintype "bidirectional"))
      (node (ref "JP1") (pin "2") (pinfunction "2_2") (pintype "bidirectional"))
      (node (ref "R22") (pin "2") (pinfunction "2_2") (pintype "passive"))
    )
    (net (code "86") (name "Net-(IC8-FB)") (class "Default")
      (node (ref "C26") (pin "2") (pinfunction "2_2") (pintype "passive"))
      (node (ref "IC8") (pin "6") (pinfunction "FB_6") (pintype "bidirectional"))
      (node (ref "R19") (pin "1") (pinfunction "1_1") (pintype "passive"))
      (node (ref "R20") (pin "2") (pinfunction "2_2") (pintype "passive"))
    )
    (net (code "87") (name "Net-(IC8-RT)") (class "Default")
      (node (ref "IC8") (pin "8") (pinfunction "RT_8") (pintype "bidirectional"))
      (node (ref "R17") (pin "1") (pinfunction "1_1") (pintype "passive"))
    )
    (net (code "88") (name "Net-(IC8-SS)") (class "Default")
      (node (ref "IC8") (pin "7") (pinfunction "SS_7") (pintype "bidirectional"))
      (node (ref "R77") (pin "1") (pinfunction "1_1") (pintype "passive"))
    )
    (net (code "89") (name "Net-(IC8-SW)") (class "Default")
      (node (ref "C25") (pin "1") (pinfunction "1_1") (pintype "passive"))
      (node (ref "D7") (pin "K") (pinfunction "K_K") (pintype "passive"))
      (node (ref "IC8") (pin "3") (pinfunction "SW_3") (pintype "bidirectional"))
      (node (ref "L9") (pin "1") (pinfunction "1_1") (pintype "passive"))
    )
    (net (code "90") (name "Net-(IC10-OUT)") (class "Default")
      (node (ref "IC10") (pin "3") (pinfunction "OUT_3") (pintype "output"))
      (node (ref "R102") (pin "1") (pinfunction "1_1") (pintype "passive"))
    )
    (net (code "91") (name "Net-(IC10-VIN+)") (class "Default")
      (node (ref "C29") (pin "1") (pinfunction "1_1") (pintype "passive"))
      (node (ref "F1") (pin "1") (pinfunction "1_1") (pintype "passive"))
      (node (ref "IC10") (pin "5") (pinfunction "VIN+_5") (pintype "input"))
      (node (ref "R39") (pin "2") (pinfunction "2_2") (pintype "passive"))
    )
    (net (code "92") (name "Net-(IC11-WP)") (class "Default")
      (node (ref "IC11") (pin "7") (pinfunction "WP_7") (pintype "input"))
      (node (ref "R18") (pin "2") (pinfunction "2_2") (pintype "passive"))
      (node (ref "TP1") (pin "P$1") (pinfunction "TP_P$1") (pintype "passive"))
    )
    (net (code "93") (name "Net-(IC13-VIN)") (class "Default")
      (node (ref "C58") (pin "1") (pinfunction "1_1") (pintype "passive"))
      (node (ref "C59") (pin "1") (pinfunction "1_1") (pintype "passive"))
      (node (ref "IC13") (pin "1") (pinfunction "VIN_1") (pintype "bidirectional"))
      (node (ref "R93") (pin "2") (pinfunction "2_2") (pintype "passive"))
    )
    (net (code "94") (name "Net-(IC16A-+IN)") (class "Default")
      (node (ref "C62") (pin "1") (pinfunction "1_1") (pintype "passive"))
      (node (ref "IC16") (pin "3") (pinfunction "+IN_3") (pintype "input"))
      (node (ref "R95") (pin "2") (pinfunction "2_2") (pintype "passive"))
      (node (ref "R96") (pin "1") (pinfunction "1_1") (pintype "passive"))
    )
    (net (code "95") (name "Net-(IC16A--IN)") (class "Default")
      (node (ref "IC16") (pin "1") (pinfunction "OUT_1") (pintype "output"))
      (node (ref "IC16") (pin "2") (pinfunction "-IN_2") (pintype "input"))
      (node (ref "R101") (pin "2") (pinfunction "2_2") (pintype "passive"))
    )
    (net (code "96") (name "Net-(IC16B-+IN)") (class "Default")
      (node (ref "C63") (pin "1") (pinfunction "1_1") (pintype "passive"))
      (node (ref "IC16") (pin "5") (pinfunction "+IN_5") (pintype "input"))
      (node (ref "R98") (pin "2") (pinfunction "2_2") (pintype "passive"))
      (node (ref "R99") (pin "1") (pinfunction "1_1") (pintype "passive"))
    )
    (net (code "97") (name "Net-(IC16B--IN)") (class "Default")
      (node (ref "IC16") (pin "6") (pinfunction "-IN_6") (pintype "input"))
      (node (ref "IC16") (pin "7") (pinfunction "OUT_7") (pintype "output"))
      (node (ref "R100") (pin "2") (pinfunction "2_2") (pintype "passive"))
    )
    (net (code "98") (name "Net-(IC16C-V+)") (class "Default")
      (node (ref "C67") (pin "1") (pinfunction "1_1") (pintype "passive"))
      (node (ref "IC16") (pin "8") (pinfunction "V+_8") (pintype "input"))
      (node (ref "R103") (pin "1") (pinfunction "1_1") (pintype "passive"))
    )
    (net (code "99") (name "Net-(J12-+5V)") (class "Default")
      (node (ref "C85") (pin "1") (pinfunction "1_1") (pintype "passive"))
      (node (ref "D6") (pin "A") (pinfunction "A_A") (pintype "passive"))
      (node (ref "IC15") (pin "4") (pinfunction "4_4") (pintype "input"))
      (node (ref "J12") (pin "1_+5V") (pinfunction "+5V_1_+5V") (pintype "bidirectional"))
      (node (ref "R128") (pin "1") (pinfunction "1_1") (pintype "passive"))
    )
    (net (code "100") (name "Net-(JP1-Pad1)") (class "Default")
      (node (ref "JP1") (pin "1") (pinfunction "1_1") (pintype "bidirectional"))
      (node (ref "R21") (pin "1") (pinfunction "1_1") (pintype "passive"))
    )
    (net (code "101") (name "Net-(L13-Pad2)") (class "Default")
      (node (ref "L13") (pin "2") (pinfunction "2_2") (pintype "passive"))
      (node (ref "R92") (pin "1") (pinfunction "1_1") (pintype "passive"))
    )
    (net (code "102") (name "Net-(Q1B-G)") (class "Default")
      (node (ref "C70") (pin "2") (pinfunction "2_2") (pintype "passive"))
      (node (ref "Q1") (pin "5") (pinfunction "G_5") (pintype "passive"))
      (node (ref "R75") (pin "1") (pinfunction "1_1") (pintype "passive"))
      (node (ref "R82") (pin "2") (pinfunction "2_2") (pintype "passive"))
    )
    (net (code "103") (name "Net-(Q1B-S)") (class "Default")
      (node (ref "Q1") (pin "4") (pinfunction "S_4") (pintype "passive"))
      (node (ref "R106") (pin "1") (pinfunction "1_1") (pintype "passive"))
    )
    (net (code "104") (name "Net-(Q2B-G)") (class "Default")
      (node (ref "C69") (pin "2") (pinfunction "2_2") (pintype "passive"))
      (node (ref "Q2") (pin "5") (pinfunction "G_5") (pintype "passive"))
      (node (ref "R24") (pin "1") (pinfunction "1_1") (pintype "passive"))
      (node (ref "R65") (pin "2") (pinfunction "2_2") (pintype "passive"))
    )
    (net (code "105") (name "Net-(Q2B-S)") (class "Default")
      (node (ref "Q2") (pin "4") (pinfunction "S_4") (pintype "passive"))
      (node (ref "R105") (pin "1") (pinfunction "1_1") (pintype "passive"))
    )
    (net (code "106") (name "Net-(Q3-Q2D1)") (class "Default")
      (node (ref "Q3") (pin "2") (pinfunction "Q2D1_2") (pintype "bidirectional"))
      (node (ref "Q3") (pin "3") (pinfunction "Q2D2_3") (pintype "bidirectional"))
      (node (ref "R6") (pin "1") (pinfunction "1_1") (pintype "passive"))
      (node (ref "R8") (pin "1") (pinfunction "1_1") (pintype "passive"))
    )
    (net (code "107") (name "Net-(Q3-Q2G)") (class "Default")
      (node (ref "Q3") (pin "6") (pinfunction "Q2G_6") (pintype "input"))
      (node (ref "R9") (pin "3") (pinfunction "1_3") (pintype "passive"))
    )
    (net (code "108") (name "Net-(Q4A-D)") (class "Default")
      (node (ref "C33") (pin "2") (pinfunction "2_2") (pintype "passive"))
      (node (ref "Q4") (pin "6") (pinfunction "D_6") (pintype "passive"))
      (node (ref "Q5") (pin "1") (pinfunction "G_1") (pintype "passive"))
      (node (ref "R42") (pin "2") (pinfunction "2_2") (pintype "passive"))
    )
    (net (code "109") (name "Net-(Q4A-S)") (class "Default")
      (node (ref "Q4") (pin "1") (pinfunction "S_1") (pintype "passive"))
      (node (ref "R40") (pin "2") (pinfunction "2_2") (pintype "passive"))
    )
    (net (code "110") (name "Net-(Q4B-D)") (class "Default")
      (node (ref "C34") (pin "2") (pinfunction "2_2") (pintype "passive"))
      (node (ref "Q4") (pin "3") (pinfunction "D_3") (pintype "passive"))
      (node (ref "Q5") (pin "3") (pinfunction "G_3") (pintype "passive"))
      (node (ref "R45") (pin "2") (pinfunction "2_2") (pintype "passive"))
    )
    (net (code "111") (name "Net-(Q4B-S)") (class "Default")
      (node (ref "Q4") (pin "4") (pinfunction "S_4") (pintype "passive"))
      (node (ref "R43") (pin "2") (pinfunction "2_2") (pintype "passive"))
    )
    (net (code "112") (name "Net-(Q5A-D)") (class "Default")
      (node (ref "F1") (pin "2") (pinfunction "2_2") (pintype "passive"))
      (node (ref "Q5") (pin "6") (pinfunction "D_6") (pintype "passive"))
      (node (ref "R35") (pin "1") (pinfunction "1_1") (pintype "passive"))
      (node (ref "R37") (pin "1") (pinfunction "1_1") (pintype "passive"))
      (node (ref "R97") (pin "1") (pinfunction "1_1") (pintype "passive"))
    )
    (net (code "113") (name "Net-(Q6A-D)") (class "Default")
      (node (ref "C8") (pin "2") (pinfunction "2_2") (pintype "passive"))
      (node (ref "Q6") (pin "6") (pinfunction "D_6") (pintype "passive"))
      (node (ref "Q7") (pin "1") (pinfunction "G_1") (pintype "passive"))
      (node (ref "R13") (pin "2") (pinfunction "2_2") (pintype "passive"))
    )
    (net (code "114") (name "Net-(Q6A-S)") (class "Default")
      (node (ref "Q6") (pin "1") (pinfunction "S_1") (pintype "passive"))
      (node (ref "R14") (pin "2") (pinfunction "2_2") (pintype "passive"))
    )
    (net (code "115") (name "Net-(R23-Pad1)") (class "Default")
      (node (ref "R23") (pin "1") (pinfunction "1_1") (pintype "passive"))
      (node (ref "R49") (pin "2") (pinfunction "2_2") (pintype "passive"))
    )
    (net (code "116") (name "Net-(R35-Pad2)") (class "Default")
      (node (ref "R35") (pin "2") (pinfunction "2_2") (pintype "passive"))
      (node (ref "R36") (pin "1") (pinfunction "1_1") (pintype "passive"))
      (node (ref "R37") (pin "2") (pinfunction "2_2") (pintype "passive"))
      (node (ref "R38") (pin "1") (pinfunction "1_1") (pintype "passive"))
    )
    (net (code "117") (name "Net-(R94-Pad2)") (class "Default")
      (node (ref "R94") (pin "2") (pinfunction "2_2") (pintype "passive"))
      (node (ref "R95") (pin "1") (pinfunction "1_1") (pintype "passive"))
    )
    (net (code "118") (name "Net-(R97-Pad2)") (class "Default")
      (node (ref "R97") (pin "2") (pinfunction "2_2") (pintype "passive"))
      (node (ref "R98") (pin "1") (pinfunction "1_1") (pintype "passive"))
    )
    (net (code "119") (name "PGND") (class "Default")
      (node (ref "C1") (pin "2") (pinfunction "2_2") (pintype "passive"))
      (node (ref "C12") (pin "2") (pinfunction "2_2") (pintype "passive"))
      (node (ref "C3") (pin "2") (pinfunction "2_2") (pintype "passive"))
      (node (ref "C38") (pin "2") (pinfunction "2_2") (pintype "passive"))
      (node (ref "C4") (pin "2") (pinfunction "2_2") (pintype "passive"))
      (node (ref "C43") (pin "2") (pinfunction "2_2") (pintype "passive"))
      (node (ref "C44") (pin "2") (pinfunction "2_2") (pintype "passive"))
      (node (ref "C5") (pin "2") (pinfunction "2_2") (pintype "passive"))
      (node (ref "C6") (pin "2") (pinfunction "2_2") (pintype "passive"))
      (node (ref "C7") (pin "2") (pinfunction "2_2") (pintype "passive"))
      (node (ref "D8") (pin "A") (pinfunction "A_A") (pintype "passive"))
      (node (ref "D9") (pin "1") (pinfunction "A_1") (pintype "passive"))
      (node (ref "IC2") (pin "1") (pinfunction "GND1_1") (pintype "input"))
      (node (ref "IC2") (pin "2") (pinfunction "GND2_2") (pintype "input"))
      (node (ref "IC2") (pin "21") (pinfunction "GND21_21") (pintype "input"))
      (node (ref "IC2") (pin "3") (pinfunction "GND3_3") (pintype "input"))
      (node (ref "IC2") (pin "4") (pinfunction "GND4_4") (pintype "input"))
      (node (ref "IC2") (pin "5") (pinfunction "GND5_5") (pintype "input"))
      (node (ref "IC2") (pin "6") (pinfunction "GND6_6") (pintype "input"))
      (node (ref "IC2") (pin "7") (pinfunction "GND7_7") (pintype "input"))
      (node (ref "IC2") (pin "8") (pinfunction "GND8_8") (pintype "input"))
      (node (ref "IC2") (pin "G") (pinfunction "GNEXP_G") (pintype "input"))
      (node (ref "J14") (pin "5") (pinfunction "5_5") (pintype "passive"))
      (node (ref "J15") (pin "5") (pinfunction "5_5") (pintype "passive"))
      (node (ref "L2") (pin "1") (pinfunction "1_1") (pintype "passive"))
      (node (ref "Q3") (pin "1") (pinfunction "Q1S_1") (pintype "bidirectional"))
      (node (ref "R1") (pin "2") (pinfunction "1_2") (pintype "passive"))
      (node (ref "R1") (pin "4") (pinfunction "1_4") (pintype "passive"))
      (node (ref "R10") (pin "1") (pinfunction "1_1") (pintype "passive"))
      (node (ref "R10") (pin "2") (pinfunction "1_2") (pintype "passive"))
      (node (ref "R10") (pin "3") (pinfunction "1_3") (pintype "passive"))
      (node (ref "R10") (pin "4") (pinfunction "1_4") (pintype "passive"))
      (node (ref "R11") (pin "7") (pinfunction "2_7") (pintype "passive"))
      (node (ref "R11") (pin "8") (pinfunction "2_8") (pintype "passive"))
      (node (ref "R3") (pin "1") (pinfunction "1_1") (pintype "passive"))
      (node (ref "R4") (pin "1") (pinfunction "1_1") (pintype "passive"))
      (node (ref "R5") (pin "1") (pinfunction "1_1") (pintype "passive"))
      (node (ref "R50") (pin "5") (pinfunction "2_5") (pintype "passive"))
      (node (ref "R50") (pin "6") (pinfunction "2_6") (pintype "passive"))
      (node (ref "R9") (pin "2") (pinfunction "1_2") (pintype "passive"))
    )
    (net (code "120") (name "VACT") (class "Default")
      (node (ref "C1") (pin "1") (pinfunction "1_1") (pintype "passive"))
      (node (ref "C37") (pin "1") (pinfunction "1_1") (pintype "passive"))
      (node (ref "C38") (pin "1") (pinfunction "1_1") (pintype "passive"))
      (node (ref "D1") (pin "1") (pinfunction "A_1") (pintype "passive"))
      (node (ref "D8") (pin "C") (pinfunction "C_C") (pintype "passive"))
      (node (ref "IC2") (pin "20") (pinfunction "VS_B_20") (pintype "input"))
      (node (ref "IC2") (pin "22") (pinfunction "VS_A_22") (pintype "input"))
      (node (ref "Q7") (pin "6") (pinfunction "D_6") (pintype "passive"))
      (node (ref "R7") (pin "3") (pinfunction "1_3") (pintype "passive"))
    )
    (net (code "121") (name "VBAT") (class "Default")
      (node (ref "C22") (pin "1") (pinfunction "1_1") (pintype "passive"))
      (node (ref "C23") (pin "1") (pinfunction "1_1") (pintype "passive"))
      (node (ref "C8") (pin "1") (pinfunction "1_1") (pintype "passive"))
      (node (ref "C83") (pin "1") (pinfunction "1_1") (pintype "passive"))
      (node (ref "C84") (pin "1") (pinfunction "1_1") (pintype "passive"))
      (node (ref "IC10") (pin "4") (pinfunction "VIN-_4") (pintype "input"))
      (node (ref "IC8") (pin "4") (pinfunction "VIN_4") (pintype "bidirectional"))
      (node (ref "JP1") (pin "3") (pinfunction "3_3") (pintype "bidirectional"))
      (node (ref "Q3") (pin "4") (pinfunction "Q2S_4") (pintype "bidirectional"))
      (node (ref "Q7") (pin "5") (pinfunction "S_5") (pintype "passive"))
      (node (ref "R13") (pin "1") (pinfunction "1_1") (pintype "passive"))
      (node (ref "R22") (pin "1") (pinfunction "1_1") (pintype "passive"))
      (node (ref "R33") (pin "2") (pinfunction "2_2") (pintype "passive"))
      (node (ref "R39") (pin "1") (pinfunction "1_1") (pintype "passive"))
      (node (ref "R9") (pin "6") (pinfunction "2_6") (pintype "passive"))
    )
    (net (code "122") (name "unconnected-(IC1-AN8{slash}RPB8{slash}CTED10{slash}RB8-Pad32)") (class "Default")
      (node (ref "IC1") (pin "32") (pinfunction "AN8/RPB8/CTED10/RB8_32") (pintype "bidirectional"))
    )
    (net (code "123") (name "unconnected-(IC1-AN9{slash}RPB9{slash}CTED4{slash}RB9-Pad33)") (class "Default")
      (node (ref "IC1") (pin "33") (pinfunction "AN9/RPB9/CTED4/RB9_33") (pintype "bidirectional"))
    )
    (net (code "124") (name "unconnected-(IC1-AN11{slash}PMA12{slash}RB11-Pad35)") (class "Default")
      (node (ref "IC1") (pin "35") (pinfunction "AN11/PMA12/RB11_35") (pintype "bidirectional"))
    )
    (net (code "125") (name "unconnected-(IC1-AN12{slash}PMA11{slash}RB12-Pad41)") (class "Default")
      (node (ref "IC1") (pin "41") (pinfunction "AN12/PMA11/RB12_41") (pintype "bidirectional"))
    )
    (net (code "126") (name "unconnected-(IC1-AN13{slash}RB13-Pad42)") (class "Default")
      (node (ref "IC1") (pin "42") (pinfunction "AN13/RB13_42") (pintype "bidirectional"))
    )
    (net (code "127") (name "unconnected-(IC1-AN14{slash}RPB14{slash}PMA1{slash}CTED5{slash}RB14-Pad43)") (class "Default")
      (node (ref "IC1") (pin "43") (pinfunction "AN14/RPB14/PMA1/CTED5/RB14_43") (pintype "bidirectional"))
    )
    (net (code "128") (name "unconnected-(IC1-AN15{slash}RPB15{slash}PMA0{slash}CTED6{slash}{slash}RB15-Pad44)") (class "Default")
      (node (ref "IC1") (pin "44") (pinfunction "AN15/RPB15/PMA0/CTED6//RB15_44") (pintype "bidirectional"))
    )
    (net (code "129") (name "unconnected-(IC1-AN20{slash}PMD2{slash}RE2-Pad98)") (class "Default")
      (node (ref "IC1") (pin "98") (pinfunction "AN20/PMD2/RE2_98") (pintype "bidirectional"))
    )
    (net (code "130") (name "unconnected-(IC1-AN21{slash}PMD4{slash}RE4-Pad100)") (class "Default")
      (node (ref "IC1") (pin "100") (pinfunction "AN21/PMD4/RE4_100") (pintype "bidirectional"))
    )
    (net (code "131") (name "unconnected-(IC1-AN22{slash}RPE5{slash}PMD5{slash}RE5-Pad3)") (class "Default")
      (node (ref "IC1") (pin "3") (pinfunction "AN22/RPE5/PMD5/RE5_3") (pintype "bidirectional"))
    )
    (net (code "132") (name "unconnected-(IC1-AN23{slash}PMD6{slash}RE6-Pad4)") (class "Default")
      (node (ref "IC1") (pin "4") (pinfunction "AN23/PMD6/RE6_4") (pintype "bidirectional"))
    )
    (net (code "133") (name "unconnected-(IC1-AN24{slash}RPD1{slash}RD1-Pad76)") (class "Default")
      (node (ref "IC1") (pin "76") (pinfunction "AN24/RPD1/RD1_76") (pintype "bidirectional"))
    )
    (net (code "134") (name "unconnected-(IC1-AN25{slash}RPD2{slash}RD2-Pad77)") (class "Default")
      (node (ref "IC1") (pin "77") (pinfunction "AN25/RPD2/RD2_77") (pintype "bidirectional"))
    )
    (net (code "135") (name "unconnected-(IC1-AN26{slash}RPD3{slash}RD3-Pad78)") (class "Default")
      (node (ref "IC1") (pin "78") (pinfunction "AN26/RPD3/RD3_78") (pintype "bidirectional"))
    )
    (net (code "136") (name "unconnected-(IC1-AN27{slash}PMD7{slash}RE7-Pad5)") (class "Default")
      (node (ref "IC1") (pin "5") (pinfunction "AN27/PMD7/RE7_5") (pintype "bidirectional"))
    )
    (net (code "137") (name "unconnected-(IC1-CVREFOUT{slash}AN10{slash}RPB10{slash}PMA13{slash}CTED11{slash}RB10-Pad34)") (class "Default")
      (node (ref "IC1") (pin "34") (pinfunction "CVREFOUT/AN10/RPB10/PMA13/CTED11/RB10_34") (pintype "bidirectional"))
    )
    (net (code "138") (name "unconnected-(IC1-PGEC3{slash}AN2{slash}C2INB{slash}RPB2{slash}CTED13{slash}RB2-Pad23)") (class "Default")
      (node (ref "IC1") (pin "23") (pinfunction "PGEC3/AN2/C2INB/RPB2/CTED13/RB2_23") (pintype "bidirectional"))
    )
    (net (code "139") (name "unconnected-(IC1-PMD0{slash}RE0-Pad93)") (class "Default")
      (node (ref "IC1") (pin "93") (pinfunction "PMD0/RE0_93") (pintype "bidirectional"))
    )
    (net (code "140") (name "unconnected-(IC1-PMD1{slash}RE1-Pad94)") (class "Default")
      (node (ref "IC1") (pin "94") (pinfunction "PMD1/RE1_94") (pintype "bidirectional"))
    )
    (net (code "141") (name "unconnected-(IC1-PMD13{slash}RD13-Pad80)") (class "Default")
      (node (ref "IC1") (pin "80") (pinfunction "PMD13/RD13_80") (pintype "bidirectional"))
    )
    (net (code "142") (name "unconnected-(IC1-PMD14{slash}RD6-Pad83)") (class "Default")
      (node (ref "IC1") (pin "83") (pinfunction "PMD14/RD6_83") (pintype "bidirectional"))
    )
    (net (code "143") (name "unconnected-(IC1-RPC1{slash}RC1-Pad6)") (class "Default")
      (node (ref "IC1") (pin "6") (pinfunction "RPC1/RC1_6") (pintype "bidirectional"))
    )
    (net (code "144") (name "unconnected-(IC1-RPC2{slash}RC2-Pad7)") (class "Default")
      (node (ref "IC1") (pin "7") (pinfunction "RPC2/RC2_7") (pintype "bidirectional"))
    )
    (net (code "145") (name "unconnected-(IC1-RPC3{slash}RC3-Pad8)") (class "Default")
      (node (ref "IC1") (pin "8") (pinfunction "RPC3/RC3_8") (pintype "bidirectional"))
    )
    (net (code "146") (name "unconnected-(IC1-RPD0{slash}INT0{slash}RD0-Pad72)") (class "Default")
      (node (ref "IC1") (pin "72") (pinfunction "RPD0/INT0/RD0_72") (pintype "bidirectional"))
    )
    (net (code "147") (name "unconnected-(IC1-RPD4{slash}PMWR{slash}RD4-Pad81)") (class "Default")
      (node (ref "IC1") (pin "81") (pinfunction "RPD4/PMWR/RD4_81") (pintype "bidirectional"))
    )
    (net (code "148") (name "unconnected-(IC1-RPD5{slash}PMRD{slash}RD5-Pad82)") (class "Default")
      (node (ref "IC1") (pin "82") (pinfunction "RPD5/PMRD/RD5_82") (pintype "bidirectional"))
    )
    (net (code "149") (name "unconnected-(IC1-RPD8{slash}RTCC{slash}RD8-Pad68)") (class "Default")
      (node (ref "IC1") (pin "68") (pinfunction "RPD8/RTCC/RD8_68") (pintype "bidirectional"))
    )
    (net (code "150") (name "unconnected-(IC1-RPD9{slash}RD9-Pad69)") (class "Default")
      (node (ref "IC1") (pin "69") (pinfunction "RPD9/RD9_69") (pintype "bidirectional"))
    )
    (net (code "151") (name "unconnected-(IC1-RPD10{slash}SCK1{slash}PMCS2{slash}RD10-Pad70)") (class "Default")
      (node (ref "IC1") (pin "70") (pinfunction "RPD10/SCK1/PMCS2/RD10_70") (pintype "bidirectional"))
    )
    (net (code "152") (name "unconnected-(IC1-RPD11{slash}PMCS1{slash}RD11-Pad71)") (class "Default")
      (node (ref "IC1") (pin "71") (pinfunction "RPD11/PMCS1/RD11_71") (pintype "bidirectional"))
    )
    (net (code "153") (name "unconnected-(IC1-RPD12{slash}PMD12{slash}RD12-Pad79)") (class "Default")
      (node (ref "IC1") (pin "79") (pinfunction "RPD12/PMD12/RD12_79") (pintype "bidirectional"))
    )
    (net (code "154") (name "unconnected-(IC1-RPD14{slash}RD14-Pad47)") (class "Default")
      (node (ref "IC1") (pin "47") (pinfunction "RPD14/RD14_47") (pintype "bidirectional"))
    )
    (net (code "155") (name "unconnected-(IC1-RPD15{slash}RD15-Pad48)") (class "Default")
      (node (ref "IC1") (pin "48") (pinfunction "RPD15/RD15_48") (pintype "bidirectional"))
    )
    (net (code "156") (name "unconnected-(IC1-RPE3{slash}PMD3{slash}RE3-Pad99)") (class "Default")
      (node (ref "IC1") (pin "99") (pinfunction "RPE3/PMD3/RE3_99") (pintype "bidirectional"))
    )
    (net (code "157") (name "unconnected-(IC1-RPE8{slash}RE8-Pad18)") (class "Default")
      (node (ref "IC1") (pin "18") (pinfunction "RPE8/RE8_18") (pintype "bidirectional"))
    )
    (net (code "158") (name "unconnected-(IC1-RPE9{slash}RE9-Pad19)") (class "Default")
      (node (ref "IC1") (pin "19") (pinfunction "RPE9/RE9_19") (pintype "bidirectional"))
    )
    (net (code "159") (name "unconnected-(IC1-RPF3{slash}USBID{slash}RF3-Pad51)") (class "Default")
      (node (ref "IC1") (pin "51") (pinfunction "RPF3/USBID/RF3_51") (pintype "bidirectional"))
    )
    (net (code "160") (name "unconnected-(IC1-RPF4{slash}PMA9{slash}RF4-Pad49)") (class "Default")
      (node (ref "IC1") (pin "49") (pinfunction "RPF4/PMA9/RF4_49") (pintype "bidirectional"))
    )
    (net (code "161") (name "unconnected-(IC1-RPF5{slash}PMA8{slash}RF5-Pad50)") (class "Default")
      (node (ref "IC1") (pin "50") (pinfunction "RPF5/PMA8/RF5_50") (pintype "bidirectional"))
    )
    (net (code "162") (name "unconnected-(IC1-RPF12{slash}RF12-Pad40)") (class "Default")
      (node (ref "IC1") (pin "40") (pinfunction "RPF12/RF12_40") (pintype "bidirectional"))
    )
    (net (code "163") (name "unconnected-(IC1-RPF13{slash}RF13-Pad39)") (class "Default")
      (node (ref "IC1") (pin "39") (pinfunction "RPF13/RF13_39") (pintype "bidirectional"))
    )
    (net (code "164") (name "unconnected-(IC1-RPG0{slash}PMD8{slash}RG0-Pad90)") (class "Default")
      (node (ref "IC1") (pin "90") (pinfunction "RPG0/PMD8/RG0_90") (pintype "bidirectional"))
    )
    (net (code "165") (name "unconnected-(IC1-RPG1{slash}PMD9{slash}RG1-Pad89)") (class "Default")
      (node (ref "IC1") (pin "89") (pinfunction "RPG1/PMD9/RG1_89") (pintype "bidirectional"))
    )
    (net (code "166") (name "unconnected-(IC1-SCL2{slash}RA2-Pad58)") (class "Default")
      (node (ref "IC1") (pin "58") (pinfunction "SCL2/RA2_58") (pintype "bidirectional"))
    )
    (net (code "167") (name "unconnected-(IC1-SDA2{slash}RA3-Pad59)") (class "Default")
      (node (ref "IC1") (pin "59") (pinfunction "SDA2/RA3_59") (pintype "bidirectional"))
    )
    (net (code "168") (name "unconnected-(IC1-SOSCI{slash}RPC13{slash}RC13-Pad73)") (class "Default")
      (node (ref "IC1") (pin "73") (pinfunction "SOSCI/RPC13/RC13_73") (pintype "bidirectional"))
    )
    (net (code "169") (name "unconnected-(IC1-SOSCO{slash}RPC14{slash}T1CK{slash}RC14-Pad74)") (class "Default")
      (node (ref "IC1") (pin "74") (pinfunction "SOSCO/RPC14/T1CK/RC14_74") (pintype "bidirectional"))
    )
    (net (code "170") (name "unconnected-(IC1-TCK{slash}CTED2{slash}RA1-Pad38)") (class "Default")
      (node (ref "IC1") (pin "38") (pinfunction "TCK/CTED2/RA1_38") (pintype "bidirectional"))
    )
    (net (code "171") (name "unconnected-(IC1-TDI{slash}CTED9{slash}RA4-Pad60)") (class "Default")
      (node (ref "IC1") (pin "60") (pinfunction "TDI/CTED9/RA4_60") (pintype "bidirectional"))
    )
    (net (code "172") (name "unconnected-(IC1-TDO{slash}RA5-Pad61)") (class "Default")
      (node (ref "IC1") (pin "61") (pinfunction "TDO/RA5_61") (pintype "bidirectional"))
    )
    (net (code "173") (name "unconnected-(IC1-TMS{slash}CTED1{slash}RA0-Pad17)") (class "Default")
      (node (ref "IC1") (pin "17") (pinfunction "TMS/CTED1/RA0_17") (pintype "bidirectional"))
    )
    (net (code "174") (name "unconnected-(IC1-TRCLK{slash}RA6-Pad91)") (class "Default")
      (node (ref "IC1") (pin "91") (pinfunction "TRCLK/RA6_91") (pintype "bidirectional"))
    )
    (net (code "175") (name "unconnected-(IC1-TRD0{slash}RG13-Pad97)") (class "Default")
      (node (ref "IC1") (pin "97") (pinfunction "TRD0/RG13_97") (pintype "bidirectional"))
    )
    (net (code "176") (name "unconnected-(IC1-TRD2{slash}RG14-Pad95)") (class "Default")
      (node (ref "IC1") (pin "95") (pinfunction "TRD2/RG14_95") (pintype "bidirectional"))
    )
    (net (code "177") (name "unconnected-(IC1-TRD3{slash}CTED8{slash}RA7-Pad92)") (class "Default")
      (node (ref "IC1") (pin "92") (pinfunction "TRD3/CTED8/RA7_92") (pintype "bidirectional"))
    )
    (net (code "178") (name "unconnected-(IC8-PG-Pad9)") (class "Default")
      (node (ref "IC8") (pin "9") (pinfunction "PG_9") (pintype "bidirectional"))
    )
    (net (code "179") (name "unconnected-(Q1A-D-Pad6)") (class "Default")
      (node (ref "Q1") (pin "6") (pinfunction "D_6") (pintype "passive"))
    )
    (net (code "180") (name "unconnected-(Q1A-D1-PadP1)") (class "Default")
      (node (ref "Q1") (pin "P1") (pinfunction "D1_P1") (pintype "passive"))
    )
    (net (code "181") (name "unconnected-(Q1A-G-Pad2)") (class "Default")
      (node (ref "Q1") (pin "2") (pinfunction "G_2") (pintype "passive"))
    )
    (net (code "182") (name "unconnected-(Q1A-S-Pad1)") (class "Default")
      (node (ref "Q1") (pin "1") (pinfunction "S_1") (pintype "passive"))
    )
    (net (code "183") (name "unconnected-(Q2A-D-Pad6)") (class "Default")
      (node (ref "Q2") (pin "6") (pinfunction "D_6") (pintype "passive"))
    )
    (net (code "184") (name "unconnected-(Q2A-D1-PadP1)") (class "Default")
      (node (ref "Q2") (pin "P1") (pinfunction "D1_P1") (pintype "passive"))
    )
    (net (code "185") (name "unconnected-(Q2A-G-Pad2)") (class "Default")
      (node (ref "Q2") (pin "2") (pinfunction "G_2") (pintype "passive"))
    )
    (net (code "186") (name "unconnected-(Q2A-S-Pad1)") (class "Default")
      (node (ref "Q2") (pin "1") (pinfunction "S_1") (pintype "passive"))
    )
    (net (code "187") (name "unconnected-(Q6B-D-Pad3)") (class "Default")
      (node (ref "Q6") (pin "3") (pinfunction "D_3") (pintype "passive"))
    )
    (net (code "188") (name "unconnected-(Q6B-G-Pad5)") (class "Default")
      (node (ref "Q6") (pin "5") (pinfunction "G_5") (pintype "passive"))
    )
    (net (code "189") (name "unconnected-(Q6B-S-Pad4)") (class "Default")
      (node (ref "Q6") (pin "4") (pinfunction "S_4") (pintype "passive"))
    )
  )
)
